# homeboard10.net
KiCad netlist of a schematic drawn in EAGLE
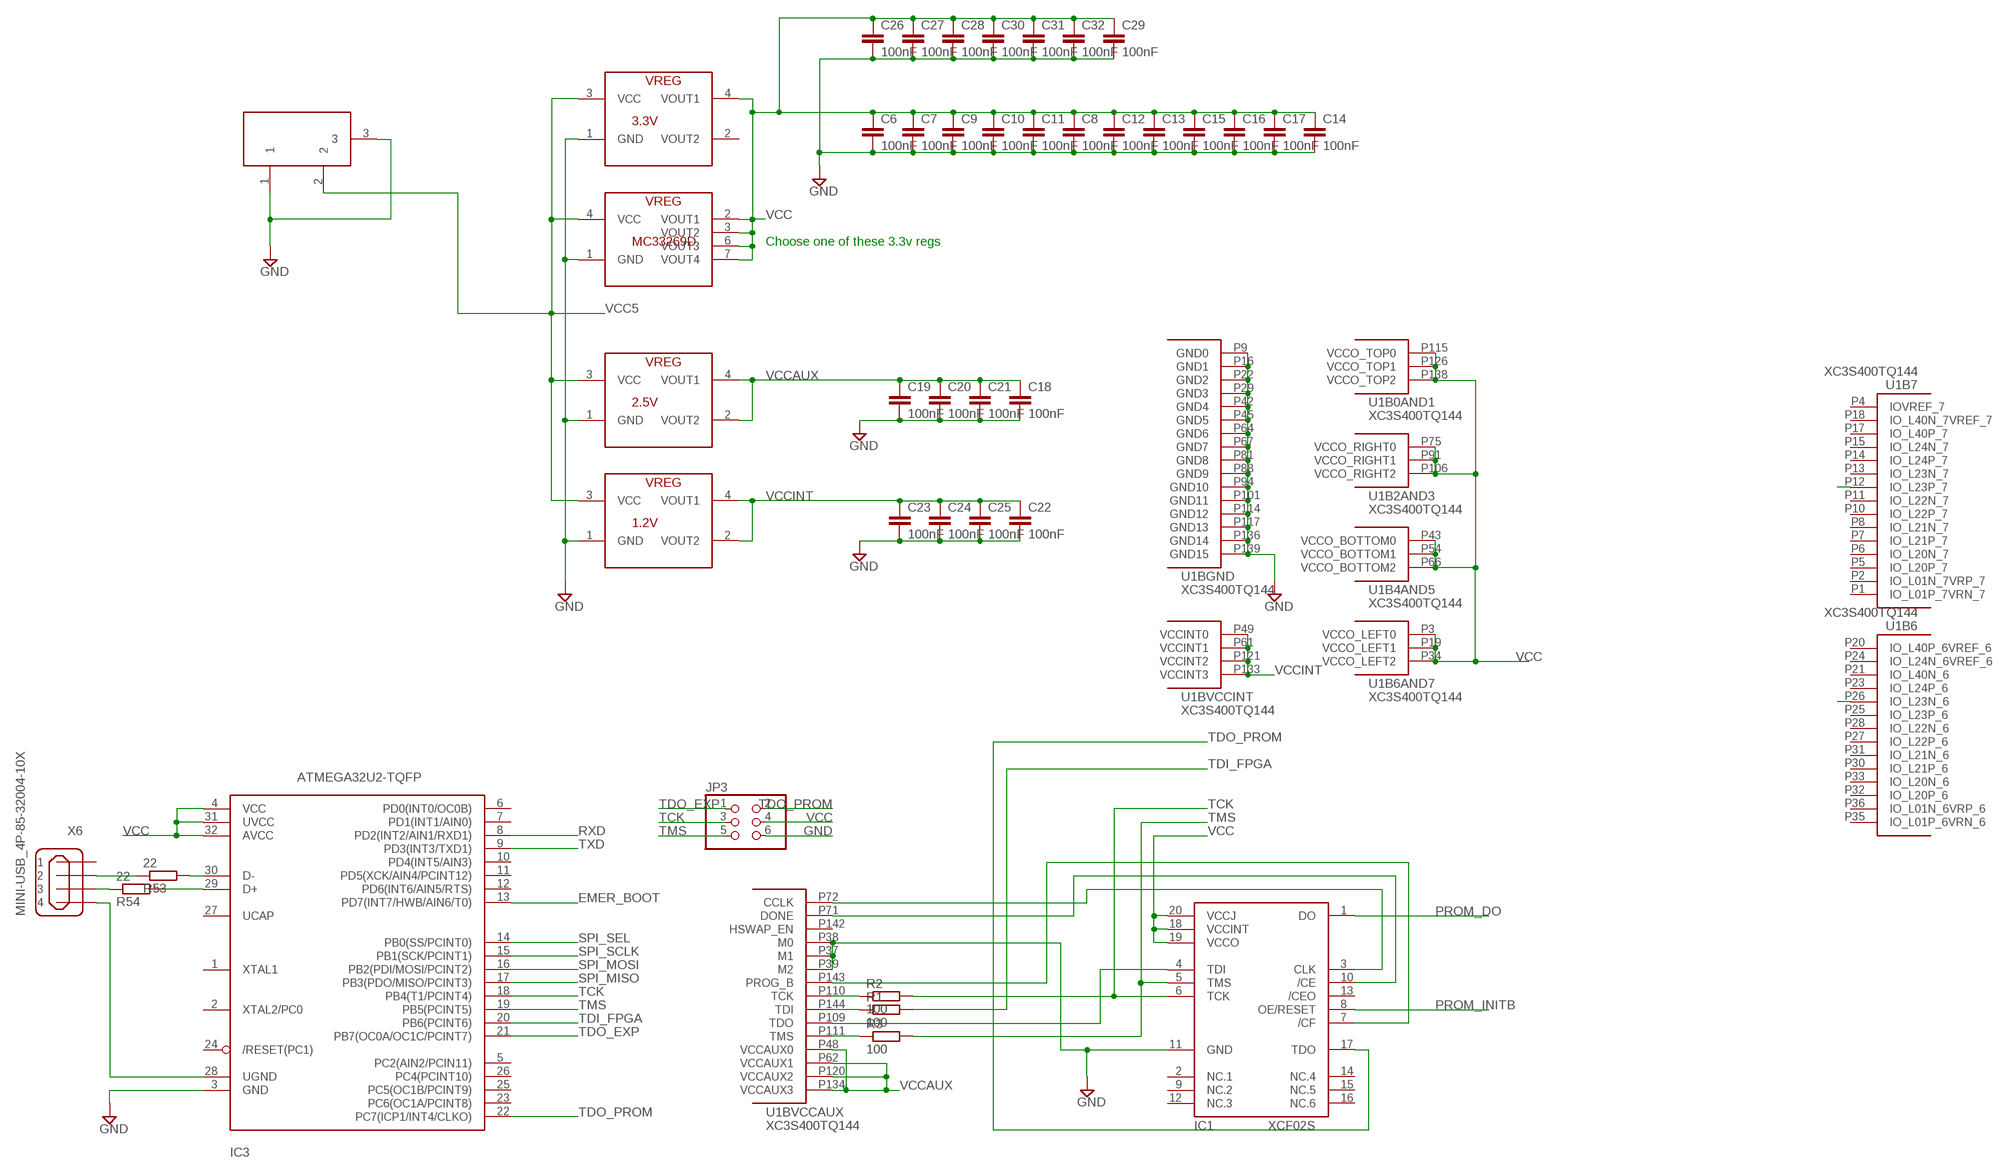
[diagram p0: schematic, sheet 1, part 1 of 3]
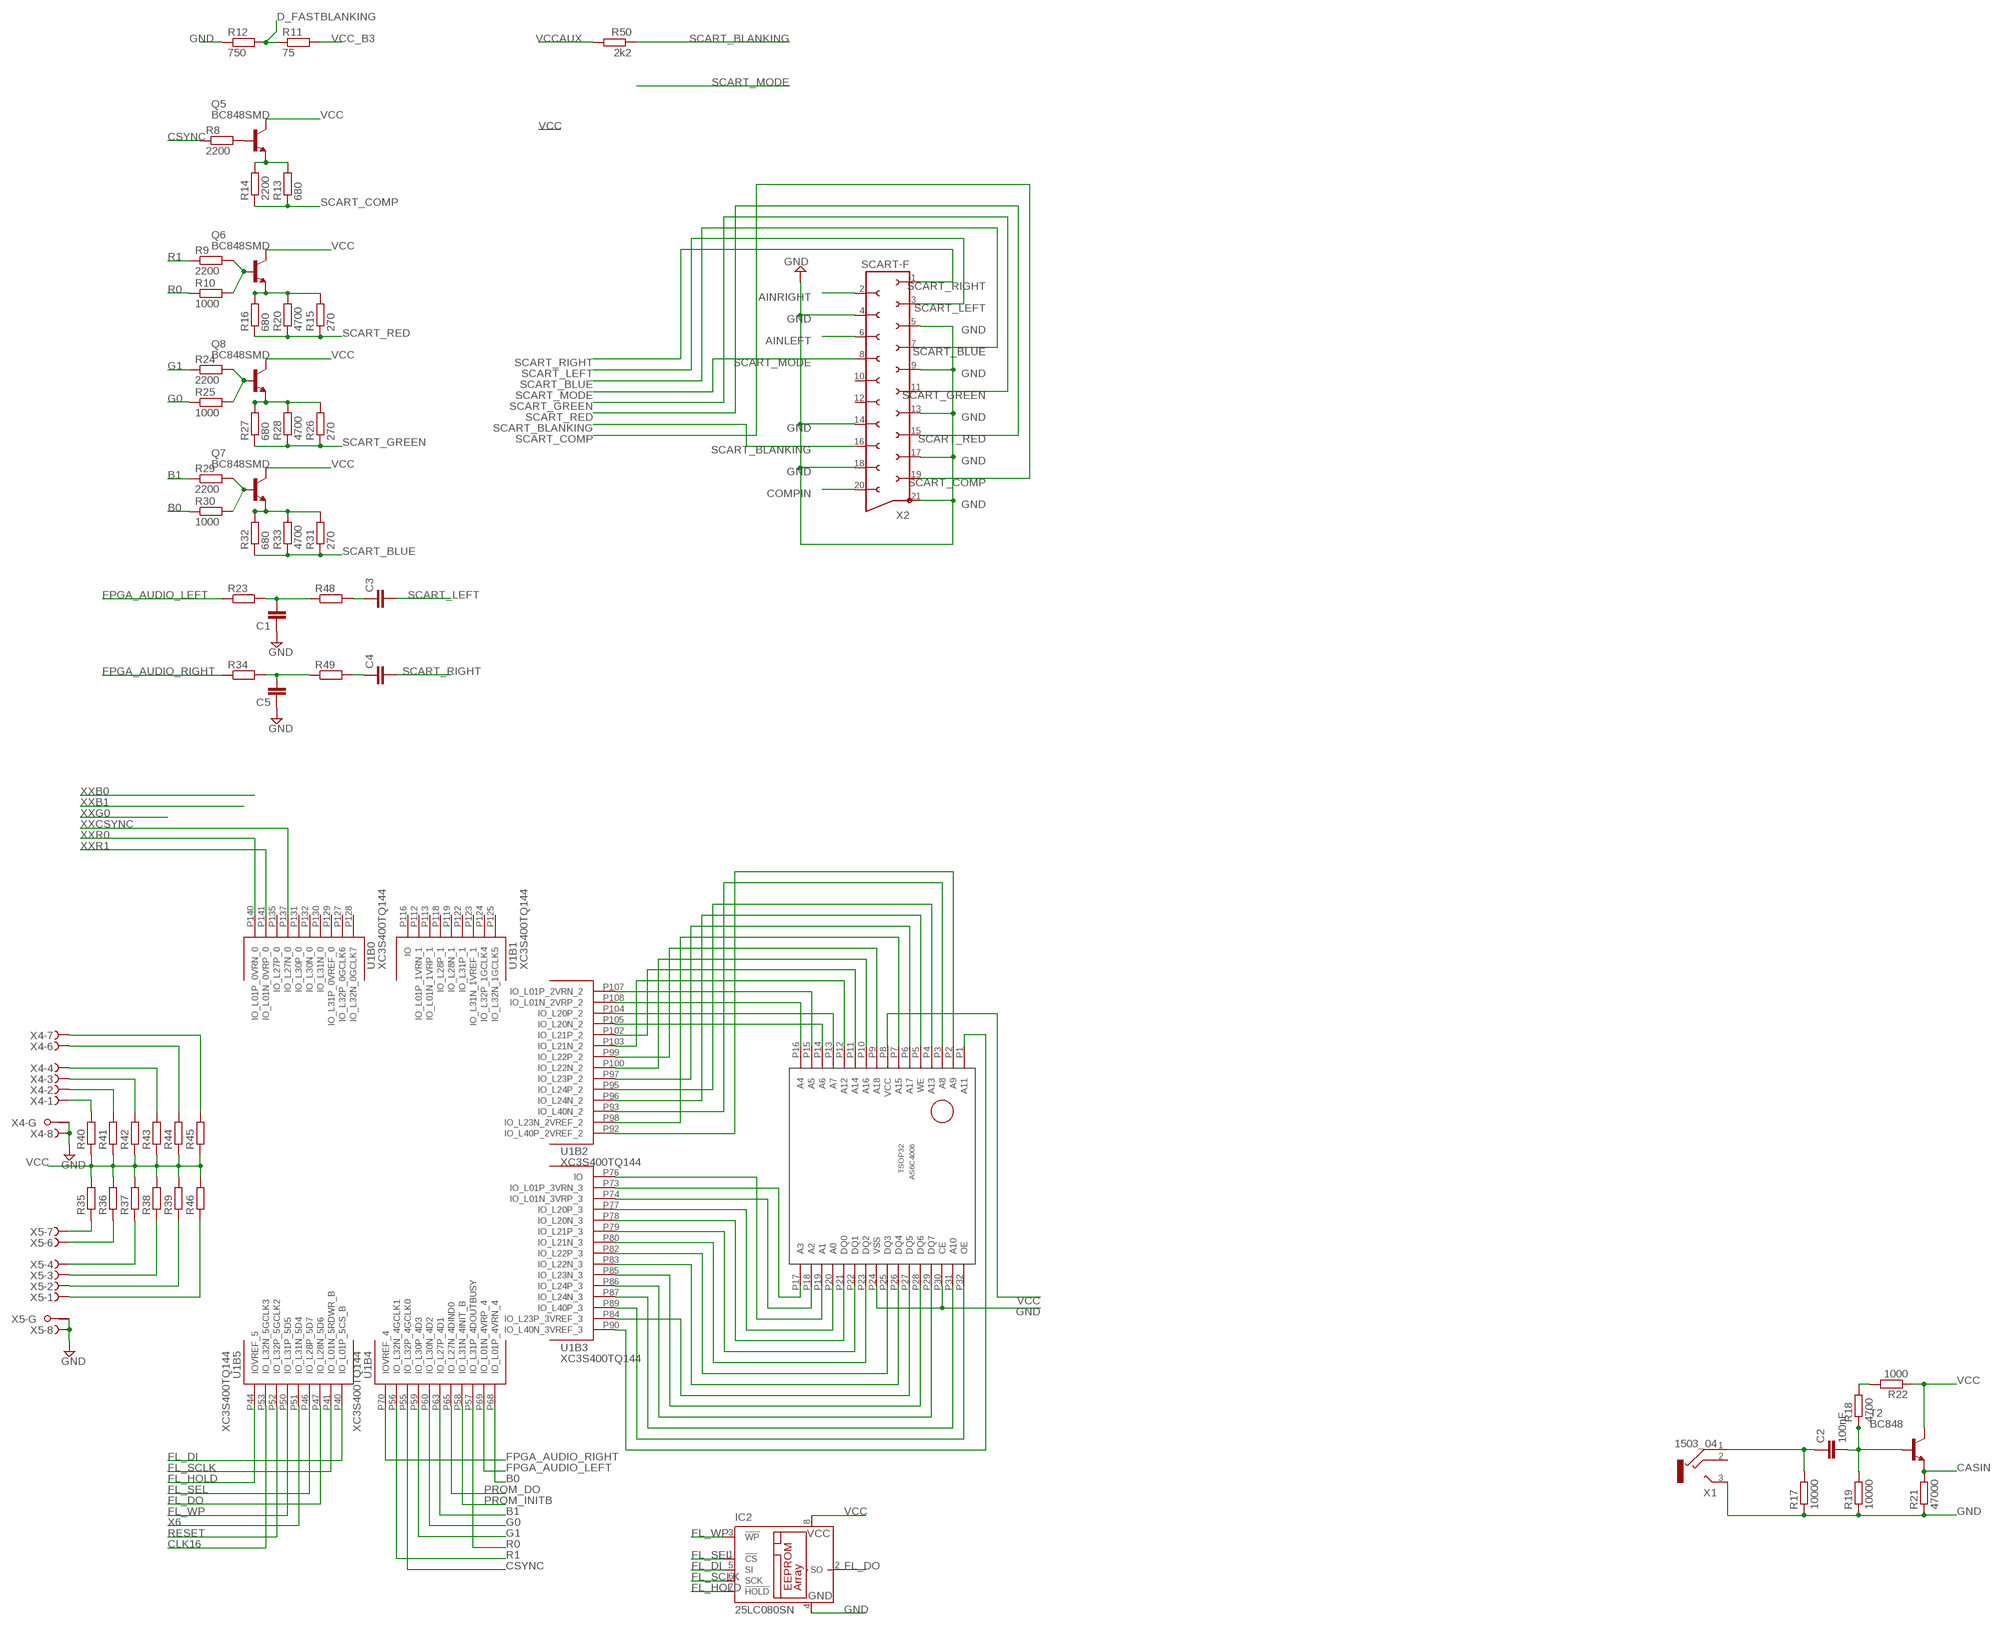
[diagram p1: schematic, sheet 1, part 2 of 3]
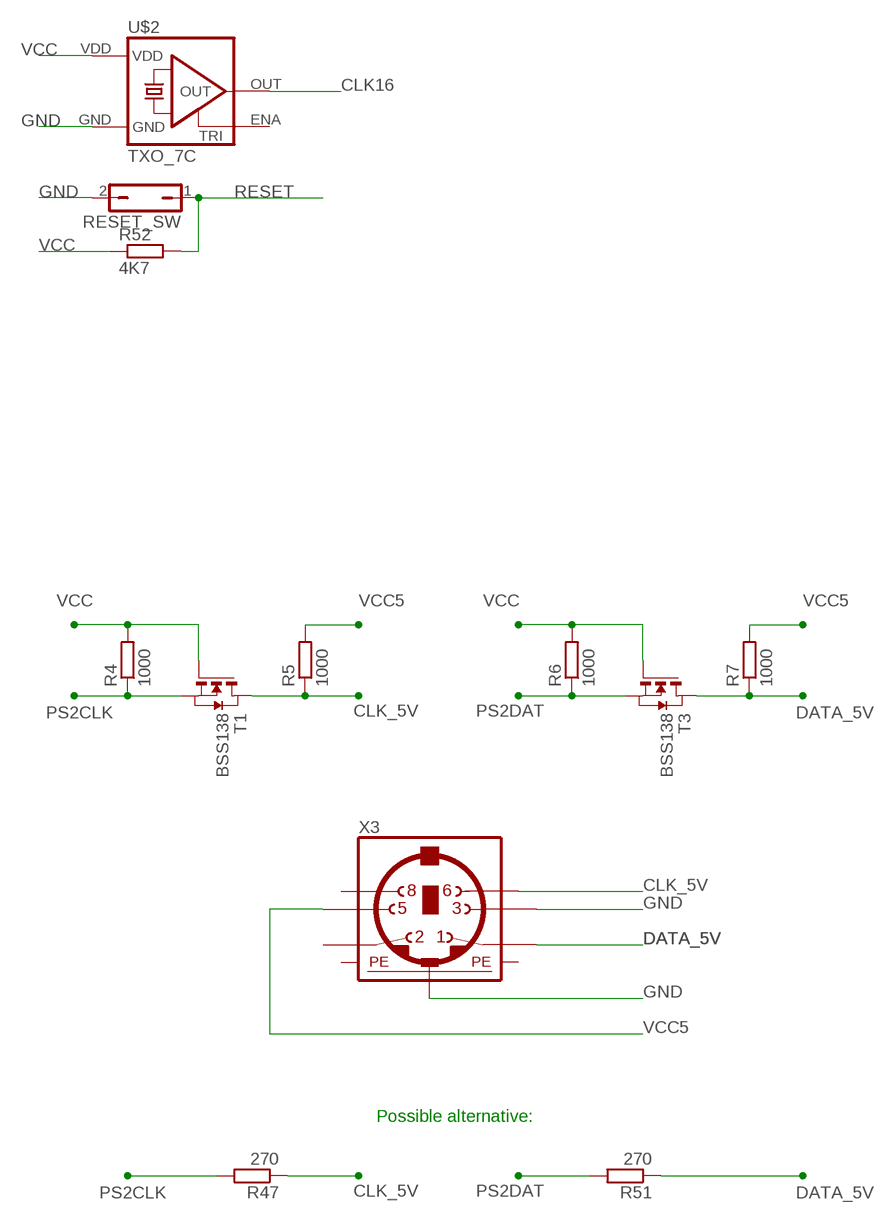
[diagram p2: schematic, sheet 1, part 3 of 3]

(export (version "E")
  (design (tool "Eeschema 10.0.6"))
  (components
    (comp (ref "C1")
      (value "C-EUC0603")
      (footprint "eagle-import:C0603")
      (libsource (lib "eagle-import") (part "resistor_C-EUC0603"))
    )
    (comp (ref "C2")
      (value "100nF")
      (footprint "eagle-import:C0603")
      (libsource (lib "eagle-import") (part "resistor_C-EUC0603"))
    )
    (comp (ref "C3")
      (value "C-EUC0603")
      (footprint "eagle-import:C0603")
      (libsource (lib "eagle-import") (part "resistor_C-EUC0603"))
    )
    (comp (ref "C4")
      (value "C-EUC0603")
      (footprint "eagle-import:C0603")
      (libsource (lib "eagle-import") (part "resistor_C-EUC0603"))
    )
    (comp (ref "C5")
      (value "C-EUC0603")
      (footprint "eagle-import:C0603")
      (libsource (lib "eagle-import") (part "resistor_C-EUC0603"))
    )
    (comp (ref "C6")
      (value "100nF")
      (footprint "eagle-import:C0603")
      (libsource (lib "eagle-import") (part "C-EUC0603"))
    )
    (comp (ref "C7")
      (value "100nF")
      (footprint "eagle-import:C0603")
      (libsource (lib "eagle-import") (part "C-EUC0603"))
    )
    (comp (ref "C8")
      (value "100nF")
      (footprint "eagle-import:C0603")
      (libsource (lib "eagle-import") (part "C-EUC0603"))
    )
    (comp (ref "C9")
      (value "100nF")
      (footprint "eagle-import:C0603")
      (libsource (lib "eagle-import") (part "C-EUC0603"))
    )
    (comp (ref "C10")
      (value "100nF")
      (footprint "eagle-import:C0603")
      (libsource (lib "eagle-import") (part "C-EUC0603"))
    )
    (comp (ref "C11")
      (value "100nF")
      (footprint "eagle-import:C0603")
      (libsource (lib "eagle-import") (part "C-EUC0603"))
    )
    (comp (ref "C12")
      (value "100nF")
      (footprint "eagle-import:C0603")
      (libsource (lib "eagle-import") (part "C-EUC0603"))
    )
    (comp (ref "C13")
      (value "100nF")
      (footprint "eagle-import:C0603")
      (libsource (lib "eagle-import") (part "C-EUC0603"))
    )
    (comp (ref "C14")
      (value "100nF")
      (footprint "eagle-import:C0603")
      (libsource (lib "eagle-import") (part "C-EUC0603"))
    )
    (comp (ref "C15")
      (value "100nF")
      (footprint "eagle-import:C0603")
      (libsource (lib "eagle-import") (part "C-EUC0603"))
    )
    (comp (ref "C16")
      (value "100nF")
      (footprint "eagle-import:C0603")
      (libsource (lib "eagle-import") (part "C-EUC0603"))
    )
    (comp (ref "C17")
      (value "100nF")
      (footprint "eagle-import:C0603")
      (libsource (lib "eagle-import") (part "C-EUC0603"))
    )
    (comp (ref "C18")
      (value "100nF")
      (footprint "eagle-import:C0603")
      (libsource (lib "eagle-import") (part "C-EUC0603"))
    )
    (comp (ref "C19")
      (value "100nF")
      (footprint "eagle-import:C0603")
      (libsource (lib "eagle-import") (part "C-EUC0603"))
    )
    (comp (ref "C20")
      (value "100nF")
      (footprint "eagle-import:C0603")
      (libsource (lib "eagle-import") (part "C-EUC0603"))
    )
    (comp (ref "C21")
      (value "100nF")
      (footprint "eagle-import:C0603")
      (libsource (lib "eagle-import") (part "C-EUC0603"))
    )
    (comp (ref "C22")
      (value "100nF")
      (footprint "eagle-import:C0603")
      (libsource (lib "eagle-import") (part "C-EUC0603"))
    )
    (comp (ref "C23")
      (value "100nF")
      (footprint "eagle-import:C0603")
      (libsource (lib "eagle-import") (part "C-EUC0603"))
    )
    (comp (ref "C24")
      (value "100nF")
      (footprint "eagle-import:C0603")
      (libsource (lib "eagle-import") (part "C-EUC0603"))
    )
    (comp (ref "C25")
      (value "100nF")
      (footprint "eagle-import:C0603")
      (libsource (lib "eagle-import") (part "C-EUC0603"))
    )
    (comp (ref "C26")
      (value "100nF")
      (footprint "eagle-import:C0603")
      (libsource (lib "eagle-import") (part "C-EUC0603"))
    )
    (comp (ref "C27")
      (value "100nF")
      (footprint "eagle-import:C0603")
      (libsource (lib "eagle-import") (part "C-EUC0603"))
    )
    (comp (ref "C28")
      (value "100nF")
      (footprint "eagle-import:C0603")
      (libsource (lib "eagle-import") (part "C-EUC0603"))
    )
    (comp (ref "C29")
      (value "100nF")
      (footprint "eagle-import:C0603")
      (libsource (lib "eagle-import") (part "C-EUC0603"))
    )
    (comp (ref "C30")
      (value "100nF")
      (footprint "eagle-import:C0603")
      (libsource (lib "eagle-import") (part "C-EUC0603"))
    )
    (comp (ref "C31")
      (value "100nF")
      (footprint "eagle-import:C0603")
      (libsource (lib "eagle-import") (part "C-EUC0603"))
    )
    (comp (ref "C32")
      (value "100nF")
      (footprint "eagle-import:C0603")
      (libsource (lib "eagle-import") (part "C-EUC0603"))
    )
    (comp (ref "IC1")
      (value "XCF02S")
      (footprint "eagle-import:VO20")
      (libsource (lib "eagle-import") (part "XCF02S"))
    )
    (comp (ref "IC2")
      (value "25LC080SN")
      (footprint "eagle-import:SO-08")
      (fields (field (name "MF") "MICROCHIP") (field (name "MPN") "25LC080/SN"))
      (libsource (lib "eagle-import") (part "25SNLC080"))
    )
    (comp (ref "IC3")
      (value "ATMEGA32U2-TQFP")
      (footprint "eagle-import:TQFP32-08")
      (libsource (lib "eagle-import") (part "ATMEGA32U2-TQFP"))
    )
    (comp (ref "JP3")
      (value "PINHD-2X3")
      (footprint "eagle-import:2X03")
      (libsource (lib "eagle-import") (part "PINHD-2X3"))
    )
    (comp (ref "Q5")
      (value "BC848SMD")
      (footprint "eagle-import:SOT23")
      (libsource (lib "eagle-import") (part "BC848SMD"))
    )
    (comp (ref "Q6")
      (value "BC848SMD")
      (footprint "eagle-import:SOT23")
      (libsource (lib "eagle-import") (part "BC848SMD"))
    )
    (comp (ref "Q7")
      (value "BC848SMD")
      (footprint "eagle-import:SOT23")
      (libsource (lib "eagle-import") (part "BC848SMD"))
    )
    (comp (ref "Q8")
      (value "BC848SMD")
      (footprint "eagle-import:SOT23")
      (libsource (lib "eagle-import") (part "BC848SMD"))
    )
    (comp (ref "R1")
      (value "100")
      (footprint "eagle-import:R0805")
      (libsource (lib "eagle-import") (part "R-EU_R0805"))
    )
    (comp (ref "R2")
      (value "100")
      (footprint "eagle-import:R0805")
      (libsource (lib "eagle-import") (part "R-EU_R0805"))
    )
    (comp (ref "R3")
      (value "100")
      (footprint "eagle-import:R0805")
      (libsource (lib "eagle-import") (part "R-EU_R0805"))
    )
    (comp (ref "R4")
      (value "1000")
      (footprint "eagle-import:R0805")
      (libsource (lib "eagle-import") (part "R-EU_R0805"))
    )
    (comp (ref "R5")
      (value "1000")
      (footprint "eagle-import:R0805")
      (libsource (lib "eagle-import") (part "R-EU_R0805"))
    )
    (comp (ref "R6")
      (value "1000")
      (footprint "eagle-import:R0805")
      (libsource (lib "eagle-import") (part "R-EU_R0805"))
    )
    (comp (ref "R7")
      (value "1000")
      (footprint "eagle-import:R0805")
      (libsource (lib "eagle-import") (part "R-EU_R0805"))
    )
    (comp (ref "R8")
      (value "2200")
      (footprint "eagle-import:R0805")
      (libsource (lib "eagle-import") (part "R-EU_R0805"))
    )
    (comp (ref "R9")
      (value "2200")
      (footprint "eagle-import:R0805")
      (libsource (lib "eagle-import") (part "R-EU_R0805"))
    )
    (comp (ref "R10")
      (value "1000")
      (footprint "eagle-import:R0805")
      (libsource (lib "eagle-import") (part "R-EU_R0805"))
    )
    (comp (ref "R11")
      (value "75")
      (footprint "eagle-import:R0805")
      (libsource (lib "eagle-import") (part "R-EU_R0805"))
    )
    (comp (ref "R12")
      (value "750")
      (footprint "eagle-import:R0805")
      (libsource (lib "eagle-import") (part "R-EU_R0805"))
    )
    (comp (ref "R13")
      (value "680")
      (footprint "eagle-import:R0805")
      (libsource (lib "eagle-import") (part "R-EU_R0805"))
    )
    (comp (ref "R14")
      (value "2200")
      (footprint "eagle-import:R0805")
      (libsource (lib "eagle-import") (part "R-EU_R0805"))
    )
    (comp (ref "R15")
      (value "270")
      (footprint "eagle-import:R0805")
      (libsource (lib "eagle-import") (part "R-EU_R0805"))
    )
    (comp (ref "R16")
      (value "680")
      (footprint "eagle-import:R0805")
      (libsource (lib "eagle-import") (part "R-EU_R0805"))
    )
    (comp (ref "R17")
      (value "10000")
      (footprint "eagle-import:R0805")
      (libsource (lib "eagle-import") (part "R-EU_R0805"))
    )
    (comp (ref "R18")
      (value "4700")
      (footprint "eagle-import:R0805")
      (libsource (lib "eagle-import") (part "R-EU_R0805"))
    )
    (comp (ref "R19")
      (value "10000")
      (footprint "eagle-import:R0805")
      (libsource (lib "eagle-import") (part "R-EU_R0805"))
    )
    (comp (ref "R20")
      (value "4700")
      (footprint "eagle-import:R0805")
      (libsource (lib "eagle-import") (part "R-EU_R0805"))
    )
    (comp (ref "R21")
      (value "47000")
      (footprint "eagle-import:R0805")
      (libsource (lib "eagle-import") (part "R-EU_R0805"))
    )
    (comp (ref "R22")
      (value "1000")
      (footprint "eagle-import:R0805")
      (libsource (lib "eagle-import") (part "R-EU_R0805"))
    )
    (comp (ref "R23")
      (value "R-EU_M0805")
      (footprint "eagle-import:M0805")
      (libsource (lib "eagle-import") (part "resistor_R-EU_M0805"))
    )
    (comp (ref "R24")
      (value "2200")
      (footprint "eagle-import:R0805")
      (libsource (lib "eagle-import") (part "R-EU_R0805"))
    )
    (comp (ref "R25")
      (value "1000")
      (footprint "eagle-import:R0805")
      (libsource (lib "eagle-import") (part "R-EU_R0805"))
    )
    (comp (ref "R26")
      (value "270")
      (footprint "eagle-import:R0805")
      (libsource (lib "eagle-import") (part "R-EU_R0805"))
    )
    (comp (ref "R27")
      (value "680")
      (footprint "eagle-import:R0805")
      (libsource (lib "eagle-import") (part "R-EU_R0805"))
    )
    (comp (ref "R28")
      (value "4700")
      (footprint "eagle-import:R0805")
      (libsource (lib "eagle-import") (part "R-EU_R0805"))
    )
    (comp (ref "R29")
      (value "2200")
      (footprint "eagle-import:R0805")
      (libsource (lib "eagle-import") (part "R-EU_R0805"))
    )
    (comp (ref "R30")
      (value "1000")
      (footprint "eagle-import:R0805")
      (libsource (lib "eagle-import") (part "R-EU_R0805"))
    )
    (comp (ref "R31")
      (value "270")
      (footprint "eagle-import:R0805")
      (libsource (lib "eagle-import") (part "R-EU_R0805"))
    )
    (comp (ref "R32")
      (value "680")
      (footprint "eagle-import:R0805")
      (libsource (lib "eagle-import") (part "R-EU_R0805"))
    )
    (comp (ref "R33")
      (value "4700")
      (footprint "eagle-import:R0805")
      (libsource (lib "eagle-import") (part "R-EU_R0805"))
    )
    (comp (ref "R34")
      (value "R-EU_M0805")
      (footprint "eagle-import:M0805")
      (libsource (lib "eagle-import") (part "resistor_R-EU_M0805"))
    )
    (comp (ref "R35")
      (value "R-EU_M0805")
      (footprint "eagle-import:M0805")
      (libsource (lib "eagle-import") (part "resistor_R-EU_M0805"))
    )
    (comp (ref "R36")
      (value "R-EU_M0805")
      (footprint "eagle-import:M0805")
      (libsource (lib "eagle-import") (part "resistor_R-EU_M0805"))
    )
    (comp (ref "R37")
      (value "R-EU_M0805")
      (footprint "eagle-import:M0805")
      (libsource (lib "eagle-import") (part "resistor_R-EU_M0805"))
    )
    (comp (ref "R38")
      (value "R-EU_M0805")
      (footprint "eagle-import:M0805")
      (libsource (lib "eagle-import") (part "resistor_R-EU_M0805"))
    )
    (comp (ref "R39")
      (value "R-EU_M0805")
      (footprint "eagle-import:M0805")
      (libsource (lib "eagle-import") (part "resistor_R-EU_M0805"))
    )
    (comp (ref "R40")
      (value "R-EU_M0805")
      (footprint "eagle-import:M0805")
      (libsource (lib "eagle-import") (part "resistor_R-EU_M0805"))
    )
    (comp (ref "R41")
      (value "R-EU_M0805")
      (footprint "eagle-import:M0805")
      (libsource (lib "eagle-import") (part "resistor_R-EU_M0805"))
    )
    (comp (ref "R42")
      (value "R-EU_M0805")
      (footprint "eagle-import:M0805")
      (libsource (lib "eagle-import") (part "resistor_R-EU_M0805"))
    )
    (comp (ref "R43")
      (value "R-EU_M0805")
      (footprint "eagle-import:M0805")
      (libsource (lib "eagle-import") (part "resistor_R-EU_M0805"))
    )
    (comp (ref "R44")
      (value "R-EU_M0805")
      (footprint "eagle-import:M0805")
      (libsource (lib "eagle-import") (part "resistor_R-EU_M0805"))
    )
    (comp (ref "R45")
      (value "R-EU_M0805")
      (footprint "eagle-import:M0805")
      (libsource (lib "eagle-import") (part "resistor_R-EU_M0805"))
    )
    (comp (ref "R46")
      (value "R-EU_M0805")
      (footprint "eagle-import:M0805")
      (libsource (lib "eagle-import") (part "resistor_R-EU_M0805"))
    )
    (comp (ref "R47")
      (value "270")
      (footprint "eagle-import:R0805")
      (libsource (lib "eagle-import") (part "R-EU_R0805"))
    )
    (comp (ref "R48")
      (value "R-EU_M0805")
      (footprint "eagle-import:M0805")
      (libsource (lib "eagle-import") (part "resistor_R-EU_M0805"))
    )
    (comp (ref "R49")
      (value "R-EU_M0805")
      (footprint "eagle-import:M0805")
      (libsource (lib "eagle-import") (part "resistor_R-EU_M0805"))
    )
    (comp (ref "R50")
      (value "2k2")
      (footprint "eagle-import:M0805")
      (libsource (lib "eagle-import") (part "resistor_R-EU_M0805"))
    )
    (comp (ref "R51")
      (value "270")
      (footprint "eagle-import:R0805")
      (libsource (lib "eagle-import") (part "R-EU_R0805"))
    )
    (comp (ref "R52")
      (value "4K7")
      (footprint "eagle-import:M0805")
      (libsource (lib "eagle-import") (part "resistor_R-EU_M0805"))
    )
    (comp (ref "R53")
      (value "22")
      (footprint "eagle-import:R0805")
      (libsource (lib "eagle-import") (part "R-EU_R0805"))
    )
    (comp (ref "R54")
      (value "22")
      (footprint "eagle-import:R0805")
      (libsource (lib "eagle-import") (part "R-EU_R0805"))
    )
    (comp (ref "REG1.2")
      (value "1.2V")
      (footprint "eagle-import:SOT223")
      (libsource (lib "eagle-import") (part "NX1117"))
    )
    (comp (ref "REG2.5")
      (value "2.5V")
      (footprint "eagle-import:SOT223")
      (libsource (lib "eagle-import") (part "NX1117"))
    )
    (comp (ref "RESET_SW")
      (value "JP1Q")
      (footprint "eagle-import:JP1")
      (libsource (lib "eagle-import") (part "JP1Q"))
    )
    (comp (ref "T1")
      (value "BSS138")
      (footprint "eagle-import:SOT-23")
      (libsource (lib "eagle-import") (part "NMOSSOT23"))
    )
    (comp (ref "T2")
      (value "BC848")
      (footprint "eagle-import:SOT23")
      (libsource (lib "eagle-import") (part "BC848"))
    )
    (comp (ref "T3")
      (value "BSS138")
      (footprint "eagle-import:SOT-23")
      (libsource (lib "eagle-import") (part "NMOSSOT23"))
    )
    (comp (ref "U$1")
      (value "AS6C4008")
      (footprint "eagle-import:TSOP32")
      (libsource (lib "eagle-import") (part "AS6C4008"))
    )
    (comp (ref "U$2")
      (value "TXO_7C")
      (footprint "eagle-import:OSC_7C")
      (libsource (lib "eagle-import") (part "TXO_7C"))
    )
    (comp (ref "U$3")
      (value "MC33269D")
      (footprint "eagle-import:SO8")
      (libsource (lib "eagle-import") (part "MC33269D"))
    )
    (comp (ref "U$4")
      (value "3.3V")
      (footprint "eagle-import:SOT223")
      (libsource (lib "eagle-import") (part "NX1117"))
    )
    (comp (ref "U1")
      (value "XC3S400TQ144")
      (footprint "eagle-import:TQ144")
      (libsource (lib "eagle-import") (part "XC3S400TQ144"))
    )
    (comp (ref "X1")
      (value "1503_04")
      (footprint "eagle-import:1503_04")
      (libsource (lib "eagle-import") (part "1503_04"))
    )
    (comp (ref "X2")
      (value "SCART-F")
      (footprint "eagle-import:SCART-F")
      (libsource (lib "eagle-import") (part "SCART-F"))
    )
    (comp (ref "X3")
      (value "MINI_DIN_6")
      (footprint "eagle-import:M_DIN6")
      (libsource (lib "eagle-import") (part "MINI_DIN_6"))
    )
    (comp (ref "X4")
      (value "F09HPS")
      (footprint "eagle-import:F09HP")
      (libsource (lib "eagle-import") (part "F09HPS"))
    )
    (comp (ref "X5")
      (value "F09HPS")
      (footprint "eagle-import:F09HP")
      (libsource (lib "eagle-import") (part "F09HPS"))
    )
    (comp (ref "X6")
      (value "MINI-USB_4P-85-32004-10X")
      (footprint "eagle-import:85-32004-10X")
      (libsource (lib "eagle-import") (part "MINI-USB_4P-85-32004-10X"))
    )
    (comp (ref "X8")
      (value "DC21MMX")
      (footprint "eagle-import:DC-21MM")
      (libsource (lib "eagle-import") (part "DC21MMX"))
    )
  )
  (nets
    (net (code "1") (name "/AINLEFT") (class "Default")
      (node (ref "X2") (pin "6") (pinfunction "6_6") (pintype "passive"))
    )
    (net (code "2") (name "/AINRIGHT") (class "Default")
      (node (ref "X2") (pin "2") (pinfunction "2_2") (pintype "passive"))
    )
    (net (code "3") (name "/B0") (class "Default")
      (node (ref "R30") (pin "1") (pinfunction "1_1") (pintype "passive"))
      (node (ref "U1") (pin "P68") (pinfunction "IO_L01P_4VRN_4_P68") (pintype "bidirectional"))
    )
    (net (code "4") (name "/B1") (class "Default")
      (node (ref "R29") (pin "1") (pinfunction "1_1") (pintype "passive"))
      (node (ref "U1") (pin "P63") (pinfunction "IO_L27P_4D1_P63") (pintype "bidirectional"))
    )
    (net (code "5") (name "/CASIN") (class "Default")
      (node (ref "R21") (pin "2") (pinfunction "2_2") (pintype "passive"))
      (node (ref "T2") (pin "2") (pinfunction "E_2") (pintype "passive"))
    )
    (net (code "6") (name "/CLK16") (class "Default")
      (node (ref "U$2") (pin "OUT") (pinfunction "OUT_OUT") (pintype "output"))
      (node (ref "U1") (pin "P53") (pinfunction "IO_L32N_5GCLK3_P53") (pintype "bidirectional"))
    )
    (net (code "7") (name "/CLK_5V") (class "Default")
      (node (ref "R47") (pin "1") (pinfunction "1_1") (pintype "passive"))
      (node (ref "R5") (pin "1") (pinfunction "1_1") (pintype "passive"))
      (node (ref "T1") (pin "1") (pinfunction "D_1") (pintype "passive"))
      (node (ref "X3") (pin "6") (pinfunction "6_6") (pintype "passive"))
    )
    (net (code "8") (name "/COMPIN") (class "Default")
      (node (ref "X2") (pin "20") (pinfunction "20_20") (pintype "passive"))
    )
    (net (code "9") (name "/CSYNC") (class "Default")
      (node (ref "R8") (pin "1") (pinfunction "1_1") (pintype "passive"))
      (node (ref "U1") (pin "P55") (pinfunction "IO_L32P_4GCLK0_P55") (pintype "bidirectional"))
    )
    (net (code "10") (name "/DATA_5V") (class "Default")
      (node (ref "R51") (pin "1") (pinfunction "1_1") (pintype "passive"))
      (node (ref "R7") (pin "1") (pinfunction "1_1") (pintype "passive"))
      (node (ref "T3") (pin "1") (pinfunction "D_1") (pintype "passive"))
      (node (ref "X3") (pin "1") (pinfunction "1_1") (pintype "passive"))
    )
    (net (code "11") (name "/D_FASTBLANKING") (class "Default")
      (node (ref "R11") (pin "1") (pinfunction "1_1") (pintype "passive"))
      (node (ref "R12") (pin "2") (pinfunction "2_2") (pintype "passive"))
    )
    (net (code "12") (name "/EMER_BOOT") (class "Default")
      (node (ref "IC3") (pin "13") (pinfunction "PD7(INT7/HWB/AIN6/T0)_13") (pintype "bidirectional"))
    )
    (net (code "13") (name "/FL_DI") (class "Default")
      (node (ref "IC2") (pin "5") (pinfunction "SI_5") (pintype "input"))
      (node (ref "U1") (pin "P40") (pinfunction "IO_L01P_5CS_B_P40") (pintype "bidirectional"))
    )
    (net (code "14") (name "/FL_DO") (class "Default")
      (node (ref "IC2") (pin "2") (pinfunction "SO_2") (pintype "bidirectional"))
      (node (ref "U1") (pin "P47") (pinfunction "IO_L28N_5D6_P47") (pintype "bidirectional"))
    )
    (net (code "15") (name "/FL_HOLD") (class "Default")
      (node (ref "IC2") (pin "7") (pinfunction "~{HOLD}_7") (pintype "input"))
      (node (ref "U1") (pin "P44") (pinfunction "IOVREF_5_P44") (pintype "bidirectional"))
    )
    (net (code "16") (name "/FL_SCLK") (class "Default")
      (node (ref "IC2") (pin "6") (pinfunction "SCK_6") (pintype "input"))
      (node (ref "U1") (pin "P41") (pinfunction "IO_L01N_5RDWR_B_P41") (pintype "bidirectional"))
    )
    (net (code "17") (name "/FL_SEL") (class "Default")
      (node (ref "IC2") (pin "1") (pinfunction "~{CS}_1") (pintype "input"))
      (node (ref "U1") (pin "P46") (pinfunction "IO_L28P_5D7_P46") (pintype "bidirectional"))
    )
    (net (code "18") (name "/FL_WP") (class "Default")
      (node (ref "IC2") (pin "3") (pinfunction "~{WP}_3") (pintype "input"))
      (node (ref "U1") (pin "P50") (pinfunction "IO_L31P_5D5_P50") (pintype "bidirectional"))
    )
    (net (code "19") (name "/FPGA_AUDIO_LEFT") (class "Default")
      (node (ref "R23") (pin "1") (pinfunction "1_1") (pintype "passive"))
      (node (ref "U1") (pin "P69") (pinfunction "IO_L01N_4VRP_4_P69") (pintype "bidirectional"))
    )
    (net (code "20") (name "/FPGA_AUDIO_RIGHT") (class "Default")
      (node (ref "R34") (pin "1") (pinfunction "1_1") (pintype "passive"))
      (node (ref "U1") (pin "P70") (pinfunction "IOVREF_4_P70") (pintype "bidirectional"))
    )
    (net (code "21") (name "/G0") (class "Default")
      (node (ref "R25") (pin "1") (pinfunction "1_1") (pintype "passive"))
      (node (ref "U1") (pin "P60") (pinfunction "IO_L30N_4D2_P60") (pintype "bidirectional"))
    )
    (net (code "22") (name "/G1") (class "Default")
      (node (ref "R24") (pin "1") (pinfunction "1_1") (pintype "passive"))
      (node (ref "U1") (pin "P59") (pinfunction "IO_L30P_4D3_P59") (pintype "bidirectional"))
    )
    (net (code "23") (name "/PE1") (class "Default")
      (node (ref "X3") (pin "SH1") (pinfunction "PE1_SH1") (pintype "power_in"))
    )
    (net (code "24") (name "/PE3") (class "Default")
      (node (ref "X3") (pin "SH3") (pinfunction "PE3_SH3") (pintype "power_in"))
    )
    (net (code "25") (name "/PROM_DO") (class "Default")
      (node (ref "IC1") (pin "1") (pinfunction "DO_1") (pintype "bidirectional"))
      (node (ref "U1") (pin "P65") (pinfunction "IO_L27N_4DIND0_P65") (pintype "bidirectional"))
    )
    (net (code "26") (name "/PROM_INITB") (class "Default")
      (node (ref "IC1") (pin "8") (pinfunction "OE/RESET_8") (pintype "bidirectional"))
      (node (ref "U1") (pin "P58") (pinfunction "IO_L31N_4INIT_B_P58") (pintype "bidirectional"))
    )
    (net (code "27") (name "/PS2CLK") (class "Default")
      (node (ref "R4") (pin "1") (pinfunction "1_1") (pintype "passive"))
      (node (ref "R47") (pin "2") (pinfunction "2_2") (pintype "passive"))
      (node (ref "T1") (pin "2") (pinfunction "S_2") (pintype "passive"))
    )
    (net (code "28") (name "/PS2DAT") (class "Default")
      (node (ref "R51") (pin "2") (pinfunction "2_2") (pintype "passive"))
      (node (ref "R6") (pin "1") (pinfunction "1_1") (pintype "passive"))
      (node (ref "T3") (pin "2") (pinfunction "S_2") (pintype "passive"))
    )
    (net (code "29") (name "/R0") (class "Default")
      (node (ref "R10") (pin "1") (pinfunction "1_1") (pintype "passive"))
      (node (ref "U1") (pin "P57") (pinfunction "IO_L31P_4DOUTBUSY_P57") (pintype "bidirectional"))
    )
    (net (code "30") (name "/R1") (class "Default")
      (node (ref "R9") (pin "1") (pinfunction "1_1") (pintype "passive"))
      (node (ref "U1") (pin "P56") (pinfunction "IO_L32N_4GCLK1_P56") (pintype "bidirectional"))
    )
    (net (code "31") (name "/RESET") (class "Default")
      (node (ref "R52") (pin "2") (pinfunction "2_2") (pintype "passive"))
      (node (ref "RESET_SW") (pin "1") (pinfunction "1_1") (pintype "passive"))
      (node (ref "U1") (pin "P52") (pinfunction "IO_L32P_5GCLK2_P52") (pintype "bidirectional"))
    )
    (net (code "32") (name "/RXD") (class "Default")
      (node (ref "IC3") (pin "8") (pinfunction "PD2(INT2/AIN1/RXD1)_8") (pintype "bidirectional"))
    )
    (net (code "33") (name "/SCART_BLANKING") (class "Default")
      (node (ref "R50") (pin "1") (pinfunction "1_1") (pintype "passive"))
      (node (ref "X2") (pin "16") (pinfunction "16_16") (pintype "passive"))
    )
    (net (code "34") (name "/SCART_BLUE") (class "Default")
      (node (ref "R31") (pin "1") (pinfunction "1_1") (pintype "passive"))
      (node (ref "R32") (pin "1") (pinfunction "1_1") (pintype "passive"))
      (node (ref "R33") (pin "1") (pinfunction "1_1") (pintype "passive"))
      (node (ref "X2") (pin "7") (pinfunction "7_7") (pintype "passive"))
    )
    (net (code "35") (name "/SCART_COMP") (class "Default")
      (node (ref "R13") (pin "1") (pinfunction "1_1") (pintype "passive"))
      (node (ref "R14") (pin "1") (pinfunction "1_1") (pintype "passive"))
      (node (ref "X2") (pin "19") (pinfunction "19_19") (pintype "passive"))
    )
    (net (code "36") (name "/SCART_GREEN") (class "Default")
      (node (ref "R26") (pin "1") (pinfunction "1_1") (pintype "passive"))
      (node (ref "R27") (pin "1") (pinfunction "1_1") (pintype "passive"))
      (node (ref "R28") (pin "1") (pinfunction "1_1") (pintype "passive"))
      (node (ref "X2") (pin "11") (pinfunction "11_11") (pintype "passive"))
    )
    (net (code "37") (name "/SCART_LEFT") (class "Default")
      (node (ref "C3") (pin "2") (pinfunction "2_2") (pintype "passive"))
      (node (ref "X2") (pin "3") (pinfunction "3_3") (pintype "passive"))
    )
    (net (code "38") (name "/SCART_MODE") (class "Default")
      (node (ref "X2") (pin "8") (pinfunction "8_8") (pintype "passive"))
    )
    (net (code "39") (name "/SCART_RED") (class "Default")
      (node (ref "R15") (pin "1") (pinfunction "1_1") (pintype "passive"))
      (node (ref "R16") (pin "1") (pinfunction "1_1") (pintype "passive"))
      (node (ref "R20") (pin "1") (pinfunction "1_1") (pintype "passive"))
      (node (ref "X2") (pin "15") (pinfunction "15_15") (pintype "passive"))
    )
    (net (code "40") (name "/SCART_RIGHT") (class "Default")
      (node (ref "C4") (pin "2") (pinfunction "2_2") (pintype "passive"))
      (node (ref "X2") (pin "1") (pinfunction "1_1") (pintype "passive"))
    )
    (net (code "41") (name "/SPI_MISO") (class "Default")
      (node (ref "IC3") (pin "17") (pinfunction "PB3(PDO/MISO/PCINT3)_17") (pintype "bidirectional"))
    )
    (net (code "42") (name "/SPI_MOSI") (class "Default")
      (node (ref "IC3") (pin "16") (pinfunction "PB2(PDI/MOSI/PCINT2)_16") (pintype "bidirectional"))
    )
    (net (code "43") (name "/SPI_SCLK") (class "Default")
      (node (ref "IC3") (pin "15") (pinfunction "PB1(SCK/PCINT1)_15") (pintype "bidirectional"))
    )
    (net (code "44") (name "/SPI_SEL") (class "Default")
      (node (ref "IC3") (pin "14") (pinfunction "PB0(SS/PCINT0)_14") (pintype "bidirectional"))
    )
    (net (code "45") (name "/TCK") (class "Default")
      (node (ref "IC1") (pin "6") (pinfunction "TCK_6") (pintype "bidirectional"))
      (node (ref "IC3") (pin "18") (pinfunction "PB4(T1/PCINT4)_18") (pintype "bidirectional"))
      (node (ref "JP3") (pin "3") (pinfunction "3_3") (pintype "passive"))
      (node (ref "R2") (pin "2") (pinfunction "2_2") (pintype "passive"))
    )
    (net (code "46") (name "/TDI_FPGA") (class "Default")
      (node (ref "IC3") (pin "20") (pinfunction "PB6(PCINT6)_20") (pintype "bidirectional"))
      (node (ref "R1") (pin "2") (pinfunction "2_2") (pintype "passive"))
    )
    (net (code "47") (name "/TDO_EXP") (class "Default")
      (node (ref "IC3") (pin "21") (pinfunction "PB7(OC0A/OC1C/PCINT7)_21") (pintype "bidirectional"))
      (node (ref "JP3") (pin "1") (pinfunction "1_1") (pintype "passive"))
    )
    (net (code "48") (name "/TDO_PROM") (class "Default")
      (node (ref "IC1") (pin "17") (pinfunction "TDO_17") (pintype "bidirectional"))
      (node (ref "IC3") (pin "22") (pinfunction "PC7(ICP1/INT4/CLKO)_22") (pintype "bidirectional"))
      (node (ref "JP3") (pin "2") (pinfunction "2_2") (pintype "passive"))
    )
    (net (code "49") (name "/TMS") (class "Default")
      (node (ref "IC1") (pin "5") (pinfunction "TMS_5") (pintype "bidirectional"))
      (node (ref "IC3") (pin "19") (pinfunction "PB5(PCINT5)_19") (pintype "bidirectional"))
      (node (ref "JP3") (pin "5") (pinfunction "5_5") (pintype "passive"))
      (node (ref "R3") (pin "2") (pinfunction "2_2") (pintype "passive"))
    )
    (net (code "50") (name "/TXD") (class "Default")
      (node (ref "IC3") (pin "9") (pinfunction "PD3(INT3/TXD1)_9") (pintype "bidirectional"))
    )
    (net (code "51") (name "/VCC") (class "Default")
      (node (ref "C10") (pin "1") (pinfunction "1_1") (pintype "passive"))
      (node (ref "C11") (pin "1") (pinfunction "1_1") (pintype "passive"))
      (node (ref "C12") (pin "1") (pinfunction "1_1") (pintype "passive"))
      (node (ref "C13") (pin "1") (pinfunction "1_1") (pintype "passive"))
      (node (ref "C14") (pin "1") (pinfunction "1_1") (pintype "passive"))
      (node (ref "C15") (pin "1") (pinfunction "1_1") (pintype "passive"))
      (node (ref "C16") (pin "1") (pinfunction "1_1") (pintype "passive"))
      (node (ref "C17") (pin "1") (pinfunction "1_1") (pintype "passive"))
      (node (ref "C26") (pin "1") (pinfunction "1_1") (pintype "passive"))
      (node (ref "C27") (pin "1") (pinfunction "1_1") (pintype "passive"))
      (node (ref "C28") (pin "1") (pinfunction "1_1") (pintype "passive"))
      (node (ref "C29") (pin "1") (pinfunction "1_1") (pintype "passive"))
      (node (ref "C30") (pin "1") (pinfunction "1_1") (pintype "passive"))
      (node (ref "C31") (pin "1") (pinfunction "1_1") (pintype "passive"))
      (node (ref "C32") (pin "1") (pinfunction "1_1") (pintype "passive"))
      (node (ref "C6") (pin "1") (pinfunction "1_1") (pintype "passive"))
      (node (ref "C7") (pin "1") (pinfunction "1_1") (pintype "passive"))
      (node (ref "C8") (pin "1") (pinfunction "1_1") (pintype "passive"))
      (node (ref "C9") (pin "1") (pinfunction "1_1") (pintype "passive"))
      (node (ref "IC1") (pin "18") (pinfunction "VCCINT_18") (pintype "bidirectional"))
      (node (ref "IC1") (pin "19") (pinfunction "VCCO_19") (pintype "bidirectional"))
      (node (ref "IC1") (pin "20") (pinfunction "VCCJ_20") (pintype "bidirectional"))
      (node (ref "IC2") (pin "8") (pinfunction "VCC_8") (pintype "power_in"))
      (node (ref "IC3") (pin "31") (pinfunction "UVCC_31") (pintype "bidirectional"))
      (node (ref "IC3") (pin "32") (pinfunction "AVCC_32") (pintype "bidirectional"))
      (node (ref "IC3") (pin "4") (pinfunction "VCC_4") (pintype "bidirectional"))
      (node (ref "JP3") (pin "4") (pinfunction "4_4") (pintype "passive"))
      (node (ref "Q5") (pin "3") (pinfunction "C_3") (pintype "passive"))
      (node (ref "Q6") (pin "3") (pinfunction "C_3") (pintype "passive"))
      (node (ref "Q7") (pin "3") (pinfunction "C_3") (pintype "passive"))
      (node (ref "Q8") (pin "3") (pinfunction "C_3") (pintype "passive"))
      (node (ref "R22") (pin "1") (pinfunction "1_1") (pintype "passive"))
      (node (ref "R35") (pin "2") (pinfunction "2_2") (pintype "passive"))
      (node (ref "R36") (pin "2") (pinfunction "2_2") (pintype "passive"))
      (node (ref "R37") (pin "2") (pinfunction "2_2") (pintype "passive"))
      (node (ref "R38") (pin "2") (pinfunction "2_2") (pintype "passive"))
      (node (ref "R39") (pin "2") (pinfunction "2_2") (pintype "passive"))
      (node (ref "R4") (pin "2") (pinfunction "2_2") (pintype "passive"))
      (node (ref "R40") (pin "1") (pinfunction "1_1") (pintype "passive"))
      (node (ref "R41") (pin "1") (pinfunction "1_1") (pintype "passive"))
      (node (ref "R42") (pin "1") (pinfunction "1_1") (pintype "passive"))
      (node (ref "R43") (pin "1") (pinfunction "1_1") (pintype "passive"))
      (node (ref "R44") (pin "1") (pinfunction "1_1") (pintype "passive"))
      (node (ref "R45") (pin "1") (pinfunction "1_1") (pintype "passive"))
      (node (ref "R46") (pin "2") (pinfunction "2_2") (pintype "passive"))
      (node (ref "R52") (pin "1") (pinfunction "1_1") (pintype "passive"))
      (node (ref "R6") (pin "2") (pinfunction "2_2") (pintype "passive"))
      (node (ref "T1") (pin "3") (pinfunction "G_3") (pintype "passive"))
      (node (ref "T2") (pin "3") (pinfunction "C_3") (pintype "passive"))
      (node (ref "T3") (pin "3") (pinfunction "G_3") (pintype "passive"))
      (node (ref "U$1") (pin "P8") (pinfunction "VCC_P8") (pintype "bidirectional"))
      (node (ref "U$2") (pin "VDD") (pinfunction "VDD_VDD") (pintype "power_in"))
      (node (ref "U$3") (pin "2") (pinfunction "VOUT1_2") (pintype "output"))
      (node (ref "U$3") (pin "3") (pinfunction "VOUT2_3") (pintype "output"))
      (node (ref "U$3") (pin "6") (pinfunction "VOUT3_6") (pintype "output"))
      (node (ref "U$3") (pin "7") (pinfunction "VOUT4_7") (pintype "output"))
      (node (ref "U$4") (pin "4") (pinfunction "VOUT1_4") (pintype "bidirectional"))
      (node (ref "U1") (pin "P106") (pinfunction "VCCO_RIGHT2_P106") (pintype "passive"))
      (node (ref "U1") (pin "P115") (pinfunction "VCCO_TOP0_P115") (pintype "passive"))
      (node (ref "U1") (pin "P126") (pinfunction "VCCO_TOP1_P126") (pintype "passive"))
      (node (ref "U1") (pin "P138") (pinfunction "VCCO_TOP2_P138") (pintype "passive"))
      (node (ref "U1") (pin "P19") (pinfunction "VCCO_LEFT1_P19") (pintype "passive"))
      (node (ref "U1") (pin "P3") (pinfunction "VCCO_LEFT0_P3") (pintype "passive"))
      (node (ref "U1") (pin "P34") (pinfunction "VCCO_LEFT2_P34") (pintype "passive"))
      (node (ref "U1") (pin "P43") (pinfunction "VCCO_BOTTOM0_P43") (pintype "passive"))
      (node (ref "U1") (pin "P54") (pinfunction "VCCO_BOTTOM1_P54") (pintype "passive"))
      (node (ref "U1") (pin "P66") (pinfunction "VCCO_BOTTOM2_P66") (pintype "passive"))
      (node (ref "U1") (pin "P75") (pinfunction "VCCO_RIGHT0_P75") (pintype "passive"))
      (node (ref "U1") (pin "P91") (pinfunction "VCCO_RIGHT1_P91") (pintype "passive"))
    )
    (net (code "52") (name "/VCC5") (class "Default")
      (node (ref "R5") (pin "2") (pinfunction "2_2") (pintype "passive"))
      (node (ref "R7") (pin "2") (pinfunction "2_2") (pintype "passive"))
      (node (ref "REG1.2") (pin "3") (pinfunction "VCC_3") (pintype "bidirectional"))
      (node (ref "REG2.5") (pin "3") (pinfunction "VCC_3") (pintype "bidirectional"))
      (node (ref "U$3") (pin "4") (pinfunction "VCC_4") (pintype "bidirectional"))
      (node (ref "U$4") (pin "3") (pinfunction "VCC_3") (pintype "bidirectional"))
      (node (ref "X3") (pin "5") (pinfunction "5_5") (pintype "passive"))
      (node (ref "X8") (pin "2") (pinfunction "2_2") (pintype "power_in"))
    )
    (net (code "53") (name "/VCCAUX") (class "Default")
      (node (ref "C18") (pin "1") (pinfunction "1_1") (pintype "passive"))
      (node (ref "C19") (pin "1") (pinfunction "1_1") (pintype "passive"))
      (node (ref "C20") (pin "1") (pinfunction "1_1") (pintype "passive"))
      (node (ref "C21") (pin "1") (pinfunction "1_1") (pintype "passive"))
      (node (ref "R50") (pin "2") (pinfunction "2_2") (pintype "passive"))
      (node (ref "REG2.5") (pin "2") (pinfunction "VOUT2_2") (pintype "bidirectional"))
      (node (ref "REG2.5") (pin "4") (pinfunction "VOUT1_4") (pintype "bidirectional"))
      (node (ref "U1") (pin "P120") (pinfunction "VCCAUX2_P120") (pintype "passive"))
      (node (ref "U1") (pin "P134") (pinfunction "VCCAUX3_P134") (pintype "passive"))
      (node (ref "U1") (pin "P48") (pinfunction "VCCAUX0_P48") (pintype "passive"))
      (node (ref "U1") (pin "P62") (pinfunction "VCCAUX1_P62") (pintype "passive"))
    )
    (net (code "54") (name "/VCCINT") (class "Default")
      (node (ref "C22") (pin "1") (pinfunction "1_1") (pintype "passive"))
      (node (ref "C23") (pin "1") (pinfunction "1_1") (pintype "passive"))
      (node (ref "C24") (pin "1") (pinfunction "1_1") (pintype "passive"))
      (node (ref "C25") (pin "1") (pinfunction "1_1") (pintype "passive"))
      (node (ref "REG1.2") (pin "2") (pinfunction "VOUT2_2") (pintype "bidirectional"))
      (node (ref "REG1.2") (pin "4") (pinfunction "VOUT1_4") (pintype "bidirectional"))
      (node (ref "U1") (pin "P121") (pinfunction "VCCINT2_P121") (pintype "passive"))
      (node (ref "U1") (pin "P133") (pinfunction "VCCINT3_P133") (pintype "passive"))
      (node (ref "U1") (pin "P49") (pinfunction "VCCINT0_P49") (pintype "passive"))
      (node (ref "U1") (pin "P61") (pinfunction "VCCINT1_P61") (pintype "passive"))
    )
    (net (code "55") (name "/VCC_B3") (class "Default")
      (node (ref "R11") (pin "2") (pinfunction "2_2") (pintype "passive"))
    )
    (net (code "56") (name "/X6") (class "Default")
      (node (ref "U1") (pin "P51") (pinfunction "IO_L31N_5D4_P51") (pintype "bidirectional"))
    )
    (net (code "59") (name "/XXCSYNC") (class "Default")
      (node (ref "U1") (pin "P137") (pinfunction "IO_L27N_0_P137") (pintype "bidirectional"))
    )
    (net (code "61") (name "/XXR0") (class "Default")
      (node (ref "U1") (pin "P140") (pinfunction "IO_L01P_0VRN_0_P140") (pintype "bidirectional"))
    )
    (net (code "62") (name "/XXR1") (class "Default")
      (node (ref "U1") (pin "P141") (pinfunction "IO_L01N_0VRP_0_P141") (pintype "bidirectional"))
    )
    (net (code "63") (name "GND") (class "Default")
      (node (ref "C1") (pin "1") (pinfunction "1_1") (pintype "passive"))
      (node (ref "C10") (pin "2") (pinfunction "2_2") (pintype "passive"))
      (node (ref "C11") (pin "2") (pinfunction "2_2") (pintype "passive"))
      (node (ref "C12") (pin "2") (pinfunction "2_2") (pintype "passive"))
      (node (ref "C13") (pin "2") (pinfunction "2_2") (pintype "passive"))
      (node (ref "C14") (pin "2") (pinfunction "2_2") (pintype "passive"))
      (node (ref "C15") (pin "2") (pinfunction "2_2") (pintype "passive"))
      (node (ref "C16") (pin "2") (pinfunction "2_2") (pintype "passive"))
      (node (ref "C17") (pin "2") (pinfunction "2_2") (pintype "passive"))
      (node (ref "C18") (pin "2") (pinfunction "2_2") (pintype "passive"))
      (node (ref "C19") (pin "2") (pinfunction "2_2") (pintype "passive"))
      (node (ref "C20") (pin "2") (pinfunction "2_2") (pintype "passive"))
      (node (ref "C21") (pin "2") (pinfunction "2_2") (pintype "passive"))
      (node (ref "C22") (pin "2") (pinfunction "2_2") (pintype "passive"))
      (node (ref "C23") (pin "2") (pinfunction "2_2") (pintype "passive"))
      (node (ref "C24") (pin "2") (pinfunction "2_2") (pintype "passive"))
      (node (ref "C25") (pin "2") (pinfunction "2_2") (pintype "passive"))
      (node (ref "C26") (pin "2") (pinfunction "2_2") (pintype "passive"))
      (node (ref "C27") (pin "2") (pinfunction "2_2") (pintype "passive"))
      (node (ref "C28") (pin "2") (pinfunction "2_2") (pintype "passive"))
      (node (ref "C29") (pin "2") (pinfunction "2_2") (pintype "passive"))
      (node (ref "C30") (pin "2") (pinfunction "2_2") (pintype "passive"))
      (node (ref "C31") (pin "2") (pinfunction "2_2") (pintype "passive"))
      (node (ref "C32") (pin "2") (pinfunction "2_2") (pintype "passive"))
      (node (ref "C5") (pin "1") (pinfunction "1_1") (pintype "passive"))
      (node (ref "C6") (pin "2") (pinfunction "2_2") (pintype "passive"))
      (node (ref "C7") (pin "2") (pinfunction "2_2") (pintype "passive"))
      (node (ref "C8") (pin "2") (pinfunction "2_2") (pintype "passive"))
      (node (ref "C9") (pin "2") (pinfunction "2_2") (pintype "passive"))
      (node (ref "IC1") (pin "11") (pinfunction "GND_11") (pintype "bidirectional"))
      (node (ref "IC2") (pin "4") (pinfunction "GND_4") (pintype "power_in"))
      (node (ref "IC3") (pin "3") (pinfunction "GND_3") (pintype "bidirectional"))
      (node (ref "JP3") (pin "6") (pinfunction "6_6") (pintype "passive"))
      (node (ref "R12") (pin "1") (pinfunction "1_1") (pintype "passive"))
      (node (ref "R17") (pin "1") (pinfunction "1_1") (pintype "passive"))
      (node (ref "R19") (pin "1") (pinfunction "1_1") (pintype "passive"))
      (node (ref "R21") (pin "1") (pinfunction "1_1") (pintype "passive"))
      (node (ref "REG1.2") (pin "1") (pinfunction "GND_1") (pintype "bidirectional"))
      (node (ref "REG2.5") (pin "1") (pinfunction "GND_1") (pintype "bidirectional"))
      (node (ref "RESET_SW") (pin "2") (pinfunction "2_2") (pintype "passive"))
      (node (ref "U$1") (pin "P24") (pinfunction "VSS_P24") (pintype "bidirectional"))
      (node (ref "U$1") (pin "P30") (pinfunction "CE_P30") (pintype "bidirectional"))
      (node (ref "U$2") (pin "GND") (pinfunction "GND_GND") (pintype "power_in"))
      (node (ref "U$3") (pin "1") (pinfunction "GND_1") (pintype "bidirectional"))
      (node (ref "U$4") (pin "1") (pinfunction "GND_1") (pintype "bidirectional"))
      (node (ref "U1") (pin "P101") (pinfunction "GND11_P101") (pintype "passive"))
      (node (ref "U1") (pin "P114") (pinfunction "GND12_P114") (pintype "passive"))
      (node (ref "U1") (pin "P117") (pinfunction "GND13_P117") (pintype "passive"))
      (node (ref "U1") (pin "P136") (pinfunction "GND14_P136") (pintype "passive"))
      (node (ref "U1") (pin "P139") (pinfunction "GND15_P139") (pintype "passive"))
      (node (ref "U1") (pin "P16") (pinfunction "GND1_P16") (pintype "passive"))
      (node (ref "U1") (pin "P22") (pinfunction "GND2_P22") (pintype "passive"))
      (node (ref "U1") (pin "P29") (pinfunction "GND3_P29") (pintype "passive"))
      (node (ref "U1") (pin "P37") (pinfunction "M1_P37") (pintype "bidirectional"))
      (node (ref "U1") (pin "P38") (pinfunction "M0_P38") (pintype "bidirectional"))
      (node (ref "U1") (pin "P39") (pinfunction "M2_P39") (pintype "bidirectional"))
      (node (ref "U1") (pin "P42") (pinfunction "GND4_P42") (pintype "passive"))
      (node (ref "U1") (pin "P45") (pinfunction "GND5_P45") (pintype "passive"))
      (node (ref "U1") (pin "P64") (pinfunction "GND6_P64") (pintype "passive"))
      (node (ref "U1") (pin "P67") (pinfunction "GND7_P67") (pintype "passive"))
      (node (ref "U1") (pin "P81") (pinfunction "GND8_P81") (pintype "passive"))
      (node (ref "U1") (pin "P88") (pinfunction "GND9_P88") (pintype "passive"))
      (node (ref "U1") (pin "P9") (pinfunction "GND0_P9") (pintype "passive"))
      (node (ref "U1") (pin "P94") (pinfunction "GND10_P94") (pintype "passive"))
      (node (ref "X1") (pin "3") (pinfunction "2_3") (pintype "passive"))
      (node (ref "X2") (pin "13") (pinfunction "13_13") (pintype "passive"))
      (node (ref "X2") (pin "14") (pinfunction "14_14") (pintype "passive"))
      (node (ref "X2") (pin "17") (pinfunction "17_17") (pintype "passive"))
      (node (ref "X2") (pin "18") (pinfunction "18_18") (pintype "passive"))
      (node (ref "X2") (pin "21") (pinfunction "21_21") (pintype "passive"))
      (node (ref "X2") (pin "4") (pinfunction "4_4") (pintype "passive"))
      (node (ref "X2") (pin "5") (pinfunction "5_5") (pintype "passive"))
      (node (ref "X2") (pin "9") (pinfunction "9_9") (pintype "passive"))
      (node (ref "X3") (pin "3") (pinfunction "3_3") (pintype "passive"))
      (node (ref "X3") (pin "SH2") (pinfunction "PE2_SH2") (pintype "power_in"))
      (node (ref "X4") (pin "8") (pinfunction "F_8") (pintype "passive"))
      (node (ref "X4") (pin "G1") (pinfunction "G1_G1") (pintype "passive"))
      (node (ref "X5") (pin "8") (pinfunction "F_8") (pintype "passive"))
      (node (ref "X5") (pin "G1") (pinfunction "G1_G1") (pintype "passive"))
      (node (ref "X8") (pin "1") (pinfunction "1_1") (pintype "power_in"))
      (node (ref "X8") (pin "3") (pinfunction "3_3") (pintype "power_in"))
    )
    (net (code "64") (name "Net-(C1-Pad2)") (class "Default")
      (node (ref "C1") (pin "2") (pinfunction "2_2") (pintype "passive"))
      (node (ref "R23") (pin "2") (pinfunction "2_2") (pintype "passive"))
      (node (ref "R48") (pin "1") (pinfunction "1_1") (pintype "passive"))
    )
    (net (code "65") (name "Net-(C2-Pad1)") (class "Default")
      (node (ref "C2") (pin "1") (pinfunction "1_1") (pintype "passive"))
      (node (ref "R17") (pin "2") (pinfunction "2_2") (pintype "passive"))
      (node (ref "X1") (pin "1") (pinfunction "1_1") (pintype "passive"))
    )
    (net (code "66") (name "Net-(C3-Pad1)") (class "Default")
      (node (ref "C3") (pin "1") (pinfunction "1_1") (pintype "passive"))
      (node (ref "R48") (pin "2") (pinfunction "2_2") (pintype "passive"))
    )
    (net (code "67") (name "Net-(C4-Pad1)") (class "Default")
      (node (ref "C4") (pin "1") (pinfunction "1_1") (pintype "passive"))
      (node (ref "R49") (pin "2") (pinfunction "2_2") (pintype "passive"))
    )
    (net (code "68") (name "Net-(C5-Pad2)") (class "Default")
      (node (ref "C5") (pin "2") (pinfunction "2_2") (pintype "passive"))
      (node (ref "R34") (pin "2") (pinfunction "2_2") (pintype "passive"))
      (node (ref "R49") (pin "1") (pinfunction "1_1") (pintype "passive"))
    )
    (net (code "69") (name "Net-(IC1-CLK)") (class "Default")
      (node (ref "IC1") (pin "3") (pinfunction "CLK_3") (pintype "bidirectional"))
      (node (ref "U1") (pin "P72") (pinfunction "CCLK_P72") (pintype "bidirectional"))
    )
    (net (code "70") (name "Net-(IC1-TDI)") (class "Default")
      (node (ref "IC1") (pin "4") (pinfunction "TDI_4") (pintype "bidirectional"))
      (node (ref "U1") (pin "P109") (pinfunction "TDO_P109") (pintype "bidirectional"))
    )
    (net (code "71") (name "Net-(IC1-{slash}CE)") (class "Default")
      (node (ref "IC1") (pin "10") (pinfunction "/CE_10") (pintype "bidirectional"))
      (node (ref "U1") (pin "P71") (pinfunction "DONE_P71") (pintype "bidirectional"))
    )
    (net (code "72") (name "Net-(IC1-{slash}CF)") (class "Default")
      (node (ref "IC1") (pin "7") (pinfunction "/CF_7") (pintype "bidirectional"))
      (node (ref "U1") (pin "P143") (pinfunction "PROG_B_P143") (pintype "bidirectional"))
    )
    (net (code "73") (name "Net-(IC3-D+)") (class "Default")
      (node (ref "IC3") (pin "29") (pinfunction "D+_29") (pintype "bidirectional"))
      (node (ref "R54") (pin "2") (pinfunction "2_2") (pintype "passive"))
    )
    (net (code "74") (name "Net-(IC3-D-)") (class "Default")
      (node (ref "IC3") (pin "30") (pinfunction "D-_30") (pintype "bidirectional"))
      (node (ref "R53") (pin "2") (pinfunction "2_2") (pintype "passive"))
    )
    (net (code "75") (name "Net-(IC3-UGND)") (class "Default")
      (node (ref "IC3") (pin "28") (pinfunction "UGND_28") (pintype "bidirectional"))
      (node (ref "X6") (pin "4") (pinfunction "4_4") (pintype "passive"))
    )
    (net (code "76") (name "Net-(Q5-B)") (class "Default")
      (node (ref "Q5") (pin "1") (pinfunction "B_1") (pintype "passive"))
      (node (ref "R8") (pin "2") (pinfunction "2_2") (pintype "passive"))
    )
    (net (code "77") (name "Net-(Q5-E)") (class "Default")
      (node (ref "Q5") (pin "2") (pinfunction "E_2") (pintype "passive"))
      (node (ref "R13") (pin "2") (pinfunction "2_2") (pintype "passive"))
      (node (ref "R14") (pin "2") (pinfunction "2_2") (pintype "passive"))
    )
    (net (code "78") (name "Net-(Q6-B)") (class "Default")
      (node (ref "Q6") (pin "1") (pinfunction "B_1") (pintype "passive"))
      (node (ref "R10") (pin "2") (pinfunction "2_2") (pintype "passive"))
      (node (ref "R9") (pin "2") (pinfunction "2_2") (pintype "passive"))
    )
    (net (code "79") (name "Net-(Q6-E)") (class "Default")
      (node (ref "Q6") (pin "2") (pinfunction "E_2") (pintype "passive"))
      (node (ref "R15") (pin "2") (pinfunction "2_2") (pintype "passive"))
      (node (ref "R16") (pin "2") (pinfunction "2_2") (pintype "passive"))
      (node (ref "R20") (pin "2") (pinfunction "2_2") (pintype "passive"))
    )
    (net (code "80") (name "Net-(Q7-B)") (class "Default")
      (node (ref "Q7") (pin "1") (pinfunction "B_1") (pintype "passive"))
      (node (ref "R29") (pin "2") (pinfunction "2_2") (pintype "passive"))
      (node (ref "R30") (pin "2") (pinfunction "2_2") (pintype "passive"))
    )
    (net (code "81") (name "Net-(Q7-E)") (class "Default")
      (node (ref "Q7") (pin "2") (pinfunction "E_2") (pintype "passive"))
      (node (ref "R31") (pin "2") (pinfunction "2_2") (pintype "passive"))
      (node (ref "R32") (pin "2") (pinfunction "2_2") (pintype "passive"))
      (node (ref "R33") (pin "2") (pinfunction "2_2") (pintype "passive"))
    )
    (net (code "82") (name "Net-(Q8-B)") (class "Default")
      (node (ref "Q8") (pin "1") (pinfunction "B_1") (pintype "passive"))
      (node (ref "R24") (pin "2") (pinfunction "2_2") (pintype "passive"))
      (node (ref "R25") (pin "2") (pinfunction "2_2") (pintype "passive"))
    )
    (net (code "83") (name "Net-(Q8-E)") (class "Default")
      (node (ref "Q8") (pin "2") (pinfunction "E_2") (pintype "passive"))
      (node (ref "R26") (pin "2") (pinfunction "2_2") (pintype "passive"))
      (node (ref "R27") (pin "2") (pinfunction "2_2") (pintype "passive"))
      (node (ref "R28") (pin "2") (pinfunction "2_2") (pintype "passive"))
    )
    (net (code "84") (name "Net-(R18-Pad2)") (class "Default")
      (node (ref "R18") (pin "2") (pinfunction "2_2") (pintype "passive"))
      (node (ref "R22") (pin "2") (pinfunction "2_2") (pintype "passive"))
    )
    (net (code "85") (name "Net-(R53-Pad1)") (class "Default")
      (node (ref "R53") (pin "1") (pinfunction "1_1") (pintype "passive"))
      (node (ref "X6") (pin "2") (pinfunction "2_2") (pintype "passive"))
    )
    (net (code "86") (name "Net-(R54-Pad1)") (class "Default")
      (node (ref "R54") (pin "1") (pinfunction "1_1") (pintype "passive"))
      (node (ref "X6") (pin "3") (pinfunction "3_3") (pintype "passive"))
    )
    (net (code "87") (name "Net-(T2-B)") (class "Default")
      (node (ref "C2") (pin "2") (pinfunction "2_2") (pintype "passive"))
      (node (ref "R18") (pin "1") (pinfunction "1_1") (pintype "passive"))
      (node (ref "R19") (pin "2") (pinfunction "2_2") (pintype "passive"))
      (node (ref "T2") (pin "1") (pinfunction "B_1") (pintype "passive"))
    )
    (net (code "88") (name "Net-(U$1-A0)") (class "Default")
      (node (ref "U$1") (pin "P20") (pinfunction "A0_P20") (pintype "bidirectional"))
      (node (ref "U1") (pin "P77") (pinfunction "IO_L20P_3_P77") (pintype "bidirectional"))
    )
    (net (code "89") (name "Net-(U$1-A1)") (class "Default")
      (node (ref "U$1") (pin "P19") (pinfunction "A1_P19") (pintype "bidirectional"))
      (node (ref "U1") (pin "P76") (pinfunction "IO_P76") (pintype "bidirectional"))
    )
    (net (code "90") (name "Net-(U$1-A2)") (class "Default")
      (node (ref "U$1") (pin "P18") (pinfunction "A2_P18") (pintype "bidirectional"))
      (node (ref "U1") (pin "P74") (pinfunction "IO_L01N_3VRP_3_P74") (pintype "bidirectional"))
    )
    (net (code "91") (name "Net-(U$1-A3)") (class "Default")
      (node (ref "U$1") (pin "P17") (pinfunction "A3_P17") (pintype "bidirectional"))
      (node (ref "U1") (pin "P73") (pinfunction "IO_L01P_3VRN_3_P73") (pintype "bidirectional"))
    )
    (net (code "92") (name "Net-(U$1-A4)") (class "Default")
      (node (ref "U$1") (pin "P16") (pinfunction "A4_P16") (pintype "bidirectional"))
      (node (ref "U1") (pin "P108") (pinfunction "IO_L01N_2VRP_2_P108") (pintype "bidirectional"))
    )
    (net (code "93") (name "Net-(U$1-A5)") (class "Default")
      (node (ref "U$1") (pin "P15") (pinfunction "A5_P15") (pintype "bidirectional"))
      (node (ref "U1") (pin "P107") (pinfunction "IO_L01P_2VRN_2_P107") (pintype "bidirectional"))
    )
    (net (code "94") (name "Net-(U$1-A6)") (class "Default")
      (node (ref "U$1") (pin "P14") (pinfunction "A6_P14") (pintype "bidirectional"))
      (node (ref "U1") (pin "P105") (pinfunction "IO_L20N_2_P105") (pintype "bidirectional"))
    )
    (net (code "95") (name "Net-(U$1-A7)") (class "Default")
      (node (ref "U$1") (pin "P13") (pinfunction "A7_P13") (pintype "bidirectional"))
      (node (ref "U1") (pin "P104") (pinfunction "IO_L20P_2_P104") (pintype "bidirectional"))
    )
    (net (code "96") (name "Net-(U$1-A8)") (class "Default")
      (node (ref "U$1") (pin "P3") (pinfunction "A8_P3") (pintype "bidirectional"))
      (node (ref "U1") (pin "P93") (pinfunction "IO_L40N_2_P93") (pintype "bidirectional"))
    )
    (net (code "97") (name "Net-(U$1-A9)") (class "Default")
      (node (ref "U$1") (pin "P2") (pinfunction "A9_P2") (pintype "bidirectional"))
      (node (ref "U1") (pin "P92") (pinfunction "IO_L40P_2VREF_2_P92") (pintype "bidirectional"))
    )
    (net (code "98") (name "Net-(U$1-A10)") (class "Default")
      (node (ref "U$1") (pin "P31") (pinfunction "A10_P31") (pintype "bidirectional"))
      (node (ref "U1") (pin "P87") (pinfunction "IO_L24N_3_P87") (pintype "bidirectional"))
    )
    (net (code "99") (name "Net-(U$1-A11)") (class "Default")
      (node (ref "U$1") (pin "P1") (pinfunction "A11_P1") (pintype "bidirectional"))
      (node (ref "U1") (pin "P90") (pinfunction "IO_L40N_3VREF_3_P90") (pintype "bidirectional"))
    )
    (net (code "100") (name "Net-(U$1-A12)") (class "Default")
      (node (ref "U$1") (pin "P12") (pinfunction "A12_P12") (pintype "bidirectional"))
      (node (ref "U1") (pin "P103") (pinfunction "IO_L21N_2_P103") (pintype "bidirectional"))
    )
    (net (code "101") (name "Net-(U$1-A13)") (class "Default")
      (node (ref "U$1") (pin "P4") (pinfunction "A13_P4") (pintype "bidirectional"))
      (node (ref "U1") (pin "P95") (pinfunction "IO_L24P_2_P95") (pintype "bidirectional"))
    )
    (net (code "102") (name "Net-(U$1-A14)") (class "Default")
      (node (ref "U$1") (pin "P11") (pinfunction "A14_P11") (pintype "bidirectional"))
      (node (ref "U1") (pin "P102") (pinfunction "IO_L21P_2_P102") (pintype "bidirectional"))
    )
    (net (code "103") (name "Net-(U$1-A15)") (class "Default")
      (node (ref "U$1") (pin "P7") (pinfunction "A15_P7") (pintype "bidirectional"))
      (node (ref "U1") (pin "P98") (pinfunction "IO_L23N_2VREF_2_P98") (pintype "bidirectional"))
    )
    (net (code "104") (name "Net-(U$1-A16)") (class "Default")
      (node (ref "U$1") (pin "P10") (pinfunction "A16_P10") (pintype "bidirectional"))
      (node (ref "U1") (pin "P100") (pinfunction "IO_L22N_2_P100") (pintype "bidirectional"))
    )
    (net (code "105") (name "Net-(U$1-A17)") (class "Default")
      (node (ref "U$1") (pin "P6") (pinfunction "A17_P6") (pintype "bidirectional"))
      (node (ref "U1") (pin "P97") (pinfunction "IO_L23P_2_P97") (pintype "bidirectional"))
    )
    (net (code "106") (name "Net-(U$1-A18)") (class "Default")
      (node (ref "U$1") (pin "P9") (pinfunction "A18_P9") (pintype "bidirectional"))
      (node (ref "U1") (pin "P99") (pinfunction "IO_L22P_2_P99") (pintype "bidirectional"))
    )
    (net (code "107") (name "Net-(U$1-DQ0)") (class "Default")
      (node (ref "U$1") (pin "P21") (pinfunction "DQ0_P21") (pintype "bidirectional"))
      (node (ref "U1") (pin "P78") (pinfunction "IO_L20N_3_P78") (pintype "bidirectional"))
    )
    (net (code "108") (name "Net-(U$1-DQ1)") (class "Default")
      (node (ref "U$1") (pin "P22") (pinfunction "DQ1_P22") (pintype "bidirectional"))
      (node (ref "U1") (pin "P79") (pinfunction "IO_L21P_3_P79") (pintype "bidirectional"))
    )
    (net (code "109") (name "Net-(U$1-DQ2)") (class "Default")
      (node (ref "U$1") (pin "P23") (pinfunction "DQ2_P23") (pintype "bidirectional"))
      (node (ref "U1") (pin "P80") (pinfunction "IO_L21N_3_P80") (pintype "bidirectional"))
    )
    (net (code "110") (name "Net-(U$1-DQ3)") (class "Default")
      (node (ref "U$1") (pin "P25") (pinfunction "DQ3_P25") (pintype "bidirectional"))
      (node (ref "U1") (pin "P82") (pinfunction "IO_L22P_3_P82") (pintype "bidirectional"))
    )
    (net (code "111") (name "Net-(U$1-DQ4)") (class "Default")
      (node (ref "U$1") (pin "P26") (pinfunction "DQ4_P26") (pintype "bidirectional"))
      (node (ref "U1") (pin "P83") (pinfunction "IO_L22N_3_P83") (pintype "bidirectional"))
    )
    (net (code "112") (name "Net-(U$1-DQ5)") (class "Default")
      (node (ref "U$1") (pin "P27") (pinfunction "DQ5_P27") (pintype "bidirectional"))
      (node (ref "U1") (pin "P84") (pinfunction "IO_L23P_3VREF_3_P84") (pintype "bidirectional"))
    )
    (net (code "113") (name "Net-(U$1-DQ6)") (class "Default")
      (node (ref "U$1") (pin "P28") (pinfunction "DQ6_P28") (pintype "bidirectional"))
      (node (ref "U1") (pin "P85") (pinfunction "IO_L23N_3_P85") (pintype "bidirectional"))
    )
    (net (code "114") (name "Net-(U$1-DQ7)") (class "Default")
      (node (ref "U$1") (pin "P29") (pinfunction "DQ7_P29") (pintype "bidirectional"))
      (node (ref "U1") (pin "P86") (pinfunction "IO_L24P_3_P86") (pintype "bidirectional"))
    )
    (net (code "115") (name "Net-(U$1-OE)") (class "Default")
      (node (ref "U$1") (pin "P32") (pinfunction "OE_P32") (pintype "bidirectional"))
      (node (ref "U1") (pin "P89") (pinfunction "IO_L40P_3_P89") (pintype "bidirectional"))
    )
    (net (code "116") (name "Net-(U$1-WE)") (class "Default")
      (node (ref "U$1") (pin "P5") (pinfunction "WE_P5") (pintype "bidirectional"))
      (node (ref "U1") (pin "P96") (pinfunction "IO_L24N_2_P96") (pintype "bidirectional"))
    )
    (net (code "117") (name "Net-(U1N-TCK)") (class "Default")
      (node (ref "R2") (pin "1") (pinfunction "1_1") (pintype "passive"))
      (node (ref "U1") (pin "P110") (pinfunction "TCK_P110") (pintype "bidirectional"))
    )
    (net (code "118") (name "Net-(U1N-TDI)") (class "Default")
      (node (ref "R1") (pin "1") (pinfunction "1_1") (pintype "passive"))
      (node (ref "U1") (pin "P144") (pinfunction "TDI_P144") (pintype "bidirectional"))
    )
    (net (code "119") (name "Net-(U1N-TMS)") (class "Default")
      (node (ref "R3") (pin "1") (pinfunction "1_1") (pintype "passive"))
      (node (ref "U1") (pin "P111") (pinfunction "TMS_P111") (pintype "bidirectional"))
    )
    (net (code "120") (name "Net-(X4A-F)") (class "Default")
      (node (ref "R40") (pin "2") (pinfunction "2_2") (pintype "passive"))
      (node (ref "X4") (pin "1") (pinfunction "F_1") (pintype "passive"))
    )
    (net (code "121") (name "Net-(X4B-F)") (class "Default")
      (node (ref "R41") (pin "2") (pinfunction "2_2") (pintype "passive"))
      (node (ref "X4") (pin "2") (pinfunction "F_2") (pintype "passive"))
    )
    (net (code "122") (name "Net-(X4C-F)") (class "Default")
      (node (ref "R42") (pin "2") (pinfunction "2_2") (pintype "passive"))
      (node (ref "X4") (pin "3") (pinfunction "F_3") (pintype "passive"))
    )
    (net (code "123") (name "Net-(X4D-F)") (class "Default")
      (node (ref "R43") (pin "2") (pinfunction "2_2") (pintype "passive"))
      (node (ref "X4") (pin "4") (pinfunction "F_4") (pintype "passive"))
    )
    (net (code "124") (name "Net-(X4F-F)") (class "Default")
      (node (ref "R44") (pin "2") (pinfunction "2_2") (pintype "passive"))
      (node (ref "X4") (pin "6") (pinfunction "F_6") (pintype "passive"))
    )
    (net (code "125") (name "Net-(X4G-F)") (class "Default")
      (node (ref "R45") (pin "2") (pinfunction "2_2") (pintype "passive"))
      (node (ref "X4") (pin "7") (pinfunction "F_7") (pintype "passive"))
    )
    (net (code "126") (name "Net-(X5A-F)") (class "Default")
      (node (ref "R46") (pin "1") (pinfunction "1_1") (pintype "passive"))
      (node (ref "X5") (pin "1") (pinfunction "F_1") (pintype "passive"))
    )
    (net (code "127") (name "Net-(X5B-F)") (class "Default")
      (node (ref "R39") (pin "1") (pinfunction "1_1") (pintype "passive"))
      (node (ref "X5") (pin "2") (pinfunction "F_2") (pintype "passive"))
    )
    (net (code "128") (name "Net-(X5C-F)") (class "Default")
      (node (ref "R38") (pin "1") (pinfunction "1_1") (pintype "passive"))
      (node (ref "X5") (pin "3") (pinfunction "F_3") (pintype "passive"))
    )
    (net (code "129") (name "Net-(X5D-F)") (class "Default")
      (node (ref "R37") (pin "1") (pinfunction "1_1") (pintype "passive"))
      (node (ref "X5") (pin "4") (pinfunction "F_4") (pintype "passive"))
    )
    (net (code "130") (name "Net-(X5F-F)") (class "Default")
      (node (ref "R36") (pin "1") (pinfunction "1_1") (pintype "passive"))
      (node (ref "X5") (pin "6") (pinfunction "F_6") (pintype "passive"))
    )
    (net (code "131") (name "Net-(X5G-F)") (class "Default")
      (node (ref "R35") (pin "1") (pinfunction "1_1") (pintype "passive"))
      (node (ref "X5") (pin "7") (pinfunction "F_7") (pintype "passive"))
    )
    (net (code "132") (name "unconnected-(IC1-NC.1-Pad2)") (class "Default")
      (node (ref "IC1") (pin "2") (pinfunction "NC.1_2") (pintype "bidirectional"))
    )
    (net (code "133") (name "unconnected-(IC1-NC.2-Pad9)") (class "Default")
      (node (ref "IC1") (pin "9") (pinfunction "NC.2_9") (pintype "bidirectional"))
    )
    (net (code "134") (name "unconnected-(IC1-NC.3-Pad12)") (class "Default")
      (node (ref "IC1") (pin "12") (pinfunction "NC.3_12") (pintype "bidirectional"))
    )
    (net (code "135") (name "unconnected-(IC1-NC.4-Pad14)") (class "Default")
      (node (ref "IC1") (pin "14") (pinfunction "NC.4_14") (pintype "bidirectional"))
    )
    (net (code "136") (name "unconnected-(IC1-NC.5-Pad15)") (class "Default")
      (node (ref "IC1") (pin "15") (pinfunction "NC.5_15") (pintype "bidirectional"))
    )
    (net (code "137") (name "unconnected-(IC1-NC.6-Pad16)") (class "Default")
      (node (ref "IC1") (pin "16") (pinfunction "NC.6_16") (pintype "bidirectional"))
    )
    (net (code "138") (name "unconnected-(IC1-{slash}CEO-Pad13)") (class "Default")
      (node (ref "IC1") (pin "13") (pinfunction "/CEO_13") (pintype "bidirectional"))
    )
    (net (code "139") (name "unconnected-(IC3-PC2(AIN2{slash}PCIN11)-Pad5)") (class "Default")
      (node (ref "IC3") (pin "5") (pinfunction "PC2(AIN2/PCIN11)_5") (pintype "bidirectional"))
    )
    (net (code "140") (name "unconnected-(IC3-PC4(PCINT10)-Pad26)") (class "Default")
      (node (ref "IC3") (pin "26") (pinfunction "PC4(PCINT10)_26") (pintype "bidirectional"))
    )
    (net (code "141") (name "unconnected-(IC3-PC5(OC1B{slash}PCINT9)-Pad25)") (class "Default")
      (node (ref "IC3") (pin "25") (pinfunction "PC5(OC1B/PCINT9)_25") (pintype "bidirectional"))
    )
    (net (code "142") (name "unconnected-(IC3-PC6(OC1A{slash}PCINT8)-Pad23)") (class "Default")
      (node (ref "IC3") (pin "23") (pinfunction "PC6(OC1A/PCINT8)_23") (pintype "bidirectional"))
    )
    (net (code "143") (name "unconnected-(IC3-PD0(INT0{slash}OC0B)-Pad6)") (class "Default")
      (node (ref "IC3") (pin "6") (pinfunction "PD0(INT0/OC0B)_6") (pintype "bidirectional"))
    )
    (net (code "144") (name "unconnected-(IC3-PD1(INT1{slash}AIN0)-Pad7)") (class "Default")
      (node (ref "IC3") (pin "7") (pinfunction "PD1(INT1/AIN0)_7") (pintype "bidirectional"))
    )
    (net (code "145") (name "unconnected-(IC3-PD4(INT5{slash}AIN3)-Pad10)") (class "Default")
      (node (ref "IC3") (pin "10") (pinfunction "PD4(INT5/AIN3)_10") (pintype "bidirectional"))
    )
    (net (code "146") (name "unconnected-(IC3-PD5(XCK{slash}AIN4{slash}PCINT12)-Pad11)") (class "Default")
      (node (ref "IC3") (pin "11") (pinfunction "PD5(XCK/AIN4/PCINT12)_11") (pintype "bidirectional"))
    )
    (net (code "147") (name "unconnected-(IC3-PD6(INT6{slash}AIN5{slash}RTS)-Pad12)") (class "Default")
      (node (ref "IC3") (pin "12") (pinfunction "PD6(INT6/AIN5/RTS)_12") (pintype "bidirectional"))
    )
    (net (code "148") (name "unconnected-(IC3-UCAP-Pad27)") (class "Default")
      (node (ref "IC3") (pin "27") (pinfunction "UCAP_27") (pintype "bidirectional"))
    )
    (net (code "149") (name "unconnected-(IC3-XTAL1-Pad1)") (class "Default")
      (node (ref "IC3") (pin "1") (pinfunction "XTAL1_1") (pintype "bidirectional"))
    )
    (net (code "150") (name "unconnected-(IC3-XTAL2{slash}PC0-Pad2)") (class "Default")
      (node (ref "IC3") (pin "2") (pinfunction "XTAL2/PC0_2") (pintype "bidirectional"))
    )
    (net (code "151") (name "unconnected-(IC3-{slash}RESET(PC1)-Pad24)") (class "Default")
      (node (ref "IC3") (pin "24") (pinfunction "/RESET(PC1)_24") (pintype "bidirectional"))
    )
    (net (code "152") (name "unconnected-(U$2-TRI-PadENA)") (class "Default")
      (node (ref "U$2") (pin "ENA") (pinfunction "TRI_ENA") (pintype "input"))
    )
    (net (code "153") (name "unconnected-(U$4-VOUT2-Pad2)") (class "Default")
      (node (ref "U$4") (pin "2") (pinfunction "VOUT2_2") (pintype "bidirectional"))
    )
    (net (code "154") (name "unconnected-(U1A-IO_L27P_0-PadP135)") (class "Default")
      (node (ref "U1") (pin "P135") (pinfunction "IO_L27P_0_P135") (pintype "bidirectional"))
    )
    (net (code "155") (name "unconnected-(U1A-IO_L30N_0-PadP132)") (class "Default")
      (node (ref "U1") (pin "P132") (pinfunction "IO_L30N_0_P132") (pintype "bidirectional"))
    )
    (net (code "156") (name "unconnected-(U1A-IO_L30P_0-PadP131)") (class "Default")
      (node (ref "U1") (pin "P131") (pinfunction "IO_L30P_0_P131") (pintype "bidirectional"))
    )
    (net (code "157") (name "unconnected-(U1A-IO_L31N_0-PadP130)") (class "Default")
      (node (ref "U1") (pin "P130") (pinfunction "IO_L31N_0_P130") (pintype "bidirectional"))
    )
    (net (code "158") (name "unconnected-(U1A-IO_L31P_0VREF_0-PadP129)") (class "Default")
      (node (ref "U1") (pin "P129") (pinfunction "IO_L31P_0VREF_0_P129") (pintype "bidirectional"))
    )
    (net (code "159") (name "unconnected-(U1A-IO_L32N_0GCLK7-PadP128)") (class "Default")
      (node (ref "U1") (pin "P128") (pinfunction "IO_L32N_0GCLK7_P128") (pintype "bidirectional"))
    )
    (net (code "160") (name "unconnected-(U1A-IO_L32P_0GCLK6-PadP127)") (class "Default")
      (node (ref "U1") (pin "P127") (pinfunction "IO_L32P_0GCLK6_P127") (pintype "bidirectional"))
    )
    (net (code "161") (name "unconnected-(U1C-IO-PadP116)") (class "Default")
      (node (ref "U1") (pin "P116") (pinfunction "IO_P116") (pintype "bidirectional"))
    )
    (net (code "162") (name "unconnected-(U1C-IO_L01N_1VRP_1-PadP113)") (class "Default")
      (node (ref "U1") (pin "P113") (pinfunction "IO_L01N_1VRP_1_P113") (pintype "bidirectional"))
    )
    (net (code "163") (name "unconnected-(U1C-IO_L01P_1VRN_1-PadP112)") (class "Default")
      (node (ref "U1") (pin "P112") (pinfunction "IO_L01P_1VRN_1_P112") (pintype "bidirectional"))
    )
    (net (code "164") (name "unconnected-(U1C-IO_L28N_1-PadP119)") (class "Default")
      (node (ref "U1") (pin "P119") (pinfunction "IO_L28N_1_P119") (pintype "bidirectional"))
    )
    (net (code "165") (name "unconnected-(U1C-IO_L28P_1-PadP118)") (class "Default")
      (node (ref "U1") (pin "P118") (pinfunction "IO_L28P_1_P118") (pintype "bidirectional"))
    )
    (net (code "166") (name "unconnected-(U1C-IO_L31N_1VREF_1-PadP123)") (class "Default")
      (node (ref "U1") (pin "P123") (pinfunction "IO_L31N_1VREF_1_P123") (pintype "bidirectional"))
    )
    (net (code "167") (name "unconnected-(U1C-IO_L31P_1-PadP122)") (class "Default")
      (node (ref "U1") (pin "P122") (pinfunction "IO_L31P_1_P122") (pintype "bidirectional"))
    )
    (net (code "168") (name "unconnected-(U1C-IO_L32N_1GCLK5-PadP125)") (class "Default")
      (node (ref "U1") (pin "P125") (pinfunction "IO_L32N_1GCLK5_P125") (pintype "bidirectional"))
    )
    (net (code "169") (name "unconnected-(U1C-IO_L32P_1GCLK4-PadP124)") (class "Default")
      (node (ref "U1") (pin "P124") (pinfunction "IO_L32P_1GCLK4_P124") (pintype "bidirectional"))
    )
    (net (code "170") (name "unconnected-(U1J-IO_L01N_6VRP_6-PadP36)") (class "Default")
      (node (ref "U1") (pin "P36") (pinfunction "IO_L01N_6VRP_6_P36") (pintype "bidirectional"))
    )
    (net (code "171") (name "unconnected-(U1J-IO_L01P_6VRN_6-PadP35)") (class "Default")
      (node (ref "U1") (pin "P35") (pinfunction "IO_L01P_6VRN_6_P35") (pintype "bidirectional"))
    )
    (net (code "172") (name "unconnected-(U1J-IO_L20N_6-PadP33)") (class "Default")
      (node (ref "U1") (pin "P33") (pinfunction "IO_L20N_6_P33") (pintype "bidirectional"))
    )
    (net (code "173") (name "unconnected-(U1J-IO_L20P_6-PadP32)") (class "Default")
      (node (ref "U1") (pin "P32") (pinfunction "IO_L20P_6_P32") (pintype "bidirectional"))
    )
    (net (code "174") (name "unconnected-(U1J-IO_L21N_6-PadP31)") (class "Default")
      (node (ref "U1") (pin "P31") (pinfunction "IO_L21N_6_P31") (pintype "bidirectional"))
    )
    (net (code "175") (name "unconnected-(U1J-IO_L21P_6-PadP30)") (class "Default")
      (node (ref "U1") (pin "P30") (pinfunction "IO_L21P_6_P30") (pintype "bidirectional"))
    )
    (net (code "176") (name "unconnected-(U1J-IO_L22N_6-PadP28)") (class "Default")
      (node (ref "U1") (pin "P28") (pinfunction "IO_L22N_6_P28") (pintype "bidirectional"))
    )
    (net (code "177") (name "unconnected-(U1J-IO_L22P_6-PadP27)") (class "Default")
      (node (ref "U1") (pin "P27") (pinfunction "IO_L22P_6_P27") (pintype "bidirectional"))
    )
    (net (code "178") (name "unconnected-(U1J-IO_L23N_6-PadP26)") (class "Default")
      (node (ref "U1") (pin "P26") (pinfunction "IO_L23N_6_P26") (pintype "bidirectional"))
    )
    (net (code "179") (name "unconnected-(U1J-IO_L23P_6-PadP25)") (class "Default")
      (node (ref "U1") (pin "P25") (pinfunction "IO_L23P_6_P25") (pintype "bidirectional"))
    )
    (net (code "180") (name "unconnected-(U1J-IO_L24N_6VREF_6-PadP24)") (class "Default")
      (node (ref "U1") (pin "P24") (pinfunction "IO_L24N_6VREF_6_P24") (pintype "bidirectional"))
    )
    (net (code "181") (name "unconnected-(U1J-IO_L24P_6-PadP23)") (class "Default")
      (node (ref "U1") (pin "P23") (pinfunction "IO_L24P_6_P23") (pintype "bidirectional"))
    )
    (net (code "182") (name "unconnected-(U1J-IO_L40N_6-PadP21)") (class "Default")
      (node (ref "U1") (pin "P21") (pinfunction "IO_L40N_6_P21") (pintype "bidirectional"))
    )
    (net (code "183") (name "unconnected-(U1J-IO_L40P_6VREF_6-PadP20)") (class "Default")
      (node (ref "U1") (pin "P20") (pinfunction "IO_L40P_6VREF_6_P20") (pintype "bidirectional"))
    )
    (net (code "184") (name "unconnected-(U1L-IOVREF_7-PadP4)") (class "Default")
      (node (ref "U1") (pin "P4") (pinfunction "IOVREF_7_P4") (pintype "bidirectional"))
    )
    (net (code "185") (name "unconnected-(U1L-IO_L01N_7VRP_7-PadP2)") (class "Default")
      (node (ref "U1") (pin "P2") (pinfunction "IO_L01N_7VRP_7_P2") (pintype "bidirectional"))
    )
    (net (code "186") (name "unconnected-(U1L-IO_L01P_7VRN_7-PadP1)") (class "Default")
      (node (ref "U1") (pin "P1") (pinfunction "IO_L01P_7VRN_7_P1") (pintype "bidirectional"))
    )
    (net (code "187") (name "unconnected-(U1L-IO_L20N_7-PadP6)") (class "Default")
      (node (ref "U1") (pin "P6") (pinfunction "IO_L20N_7_P6") (pintype "bidirectional"))
    )
    (net (code "188") (name "unconnected-(U1L-IO_L20P_7-PadP5)") (class "Default")
      (node (ref "U1") (pin "P5") (pinfunction "IO_L20P_7_P5") (pintype "bidirectional"))
    )
    (net (code "189") (name "unconnected-(U1L-IO_L21N_7-PadP8)") (class "Default")
      (node (ref "U1") (pin "P8") (pinfunction "IO_L21N_7_P8") (pintype "bidirectional"))
    )
    (net (code "190") (name "unconnected-(U1L-IO_L21P_7-PadP7)") (class "Default")
      (node (ref "U1") (pin "P7") (pinfunction "IO_L21P_7_P7") (pintype "bidirectional"))
    )
    (net (code "191") (name "unconnected-(U1L-IO_L22N_7-PadP11)") (class "Default")
      (node (ref "U1") (pin "P11") (pinfunction "IO_L22N_7_P11") (pintype "bidirectional"))
    )
    (net (code "192") (name "unconnected-(U1L-IO_L22P_7-PadP10)") (class "Default")
      (node (ref "U1") (pin "P10") (pinfunction "IO_L22P_7_P10") (pintype "bidirectional"))
    )
    (net (code "193") (name "unconnected-(U1L-IO_L23N_7-PadP13)") (class "Default")
      (node (ref "U1") (pin "P13") (pinfunction "IO_L23N_7_P13") (pintype "bidirectional"))
    )
    (net (code "194") (name "unconnected-(U1L-IO_L23P_7-PadP12)") (class "Default")
      (node (ref "U1") (pin "P12") (pinfunction "IO_L23P_7_P12") (pintype "bidirectional"))
    )
    (net (code "195") (name "unconnected-(U1L-IO_L24N_7-PadP15)") (class "Default")
      (node (ref "U1") (pin "P15") (pinfunction "IO_L24N_7_P15") (pintype "bidirectional"))
    )
    (net (code "196") (name "unconnected-(U1L-IO_L24P_7-PadP14)") (class "Default")
      (node (ref "U1") (pin "P14") (pinfunction "IO_L24P_7_P14") (pintype "bidirectional"))
    )
    (net (code "197") (name "unconnected-(U1L-IO_L40N_7VREF_7-PadP18)") (class "Default")
      (node (ref "U1") (pin "P18") (pinfunction "IO_L40N_7VREF_7_P18") (pintype "bidirectional"))
    )
    (net (code "198") (name "unconnected-(U1L-IO_L40P_7-PadP17)") (class "Default")
      (node (ref "U1") (pin "P17") (pinfunction "IO_L40P_7_P17") (pintype "bidirectional"))
    )
    (net (code "199") (name "unconnected-(U1N-HSWAP_EN-PadP142)") (class "Default")
      (node (ref "U1") (pin "P142") (pinfunction "HSWAP_EN_P142") (pintype "bidirectional"))
    )
    (net (code "200") (name "unconnected-(X1-3-Pad2)") (class "Default")
      (node (ref "X1") (pin "2") (pinfunction "3_2") (pintype "passive"))
    )
    (net (code "201") (name "unconnected-(X2-Pad10)") (class "Default")
      (node (ref "X2") (pin "10") (pinfunction "10_10") (pintype "passive"))
    )
    (net (code "202") (name "unconnected-(X2-Pad12)") (class "Default")
      (node (ref "X2") (pin "12") (pinfunction "12_12") (pintype "passive"))
    )
    (net (code "203") (name "unconnected-(X3-Pad2)") (class "Default")
      (node (ref "X3") (pin "2") (pinfunction "2_2") (pintype "passive"))
    )
    (net (code "204") (name "unconnected-(X3-Pad8)") (class "Default")
      (node (ref "X3") (pin "8") (pinfunction "8_8") (pintype "passive"))
    )
    (net (code "205") (name "unconnected-(X4-PadG2)") (class "Default")
      (node (ref "X4") (pin "G2") (pinfunction "G2_G2") (pintype "passive"))
    )
    (net (code "206") (name "unconnected-(X5-PadG2)") (class "Default")
      (node (ref "X5") (pin "G2") (pinfunction "G2_G2") (pintype "passive"))
    )
    (net (code "207") (name "unconnected-(X6-Pad1)") (class "Default")
      (node (ref "X6") (pin "1") (pinfunction "1_1") (pintype "passive"))
    )
  )
)
